# schematic.net
KiCad netlist of a schematic drawn in EAGLE
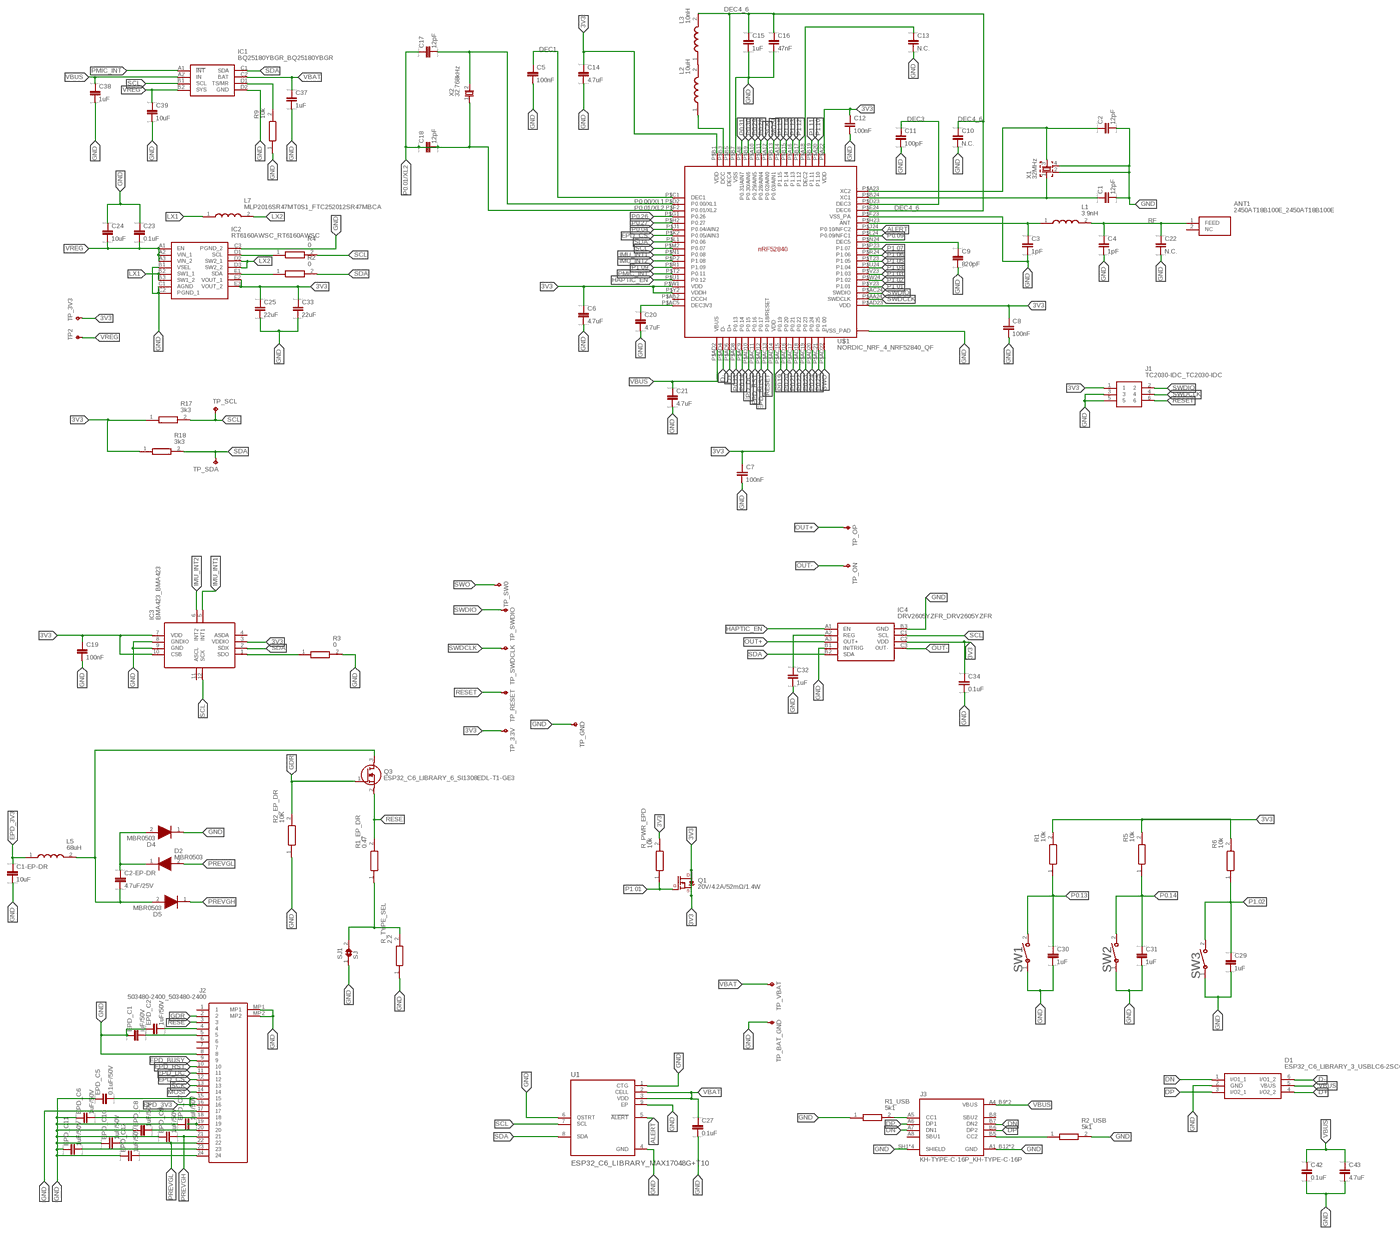
[diagram p0: schematic, sheet 1, overview]
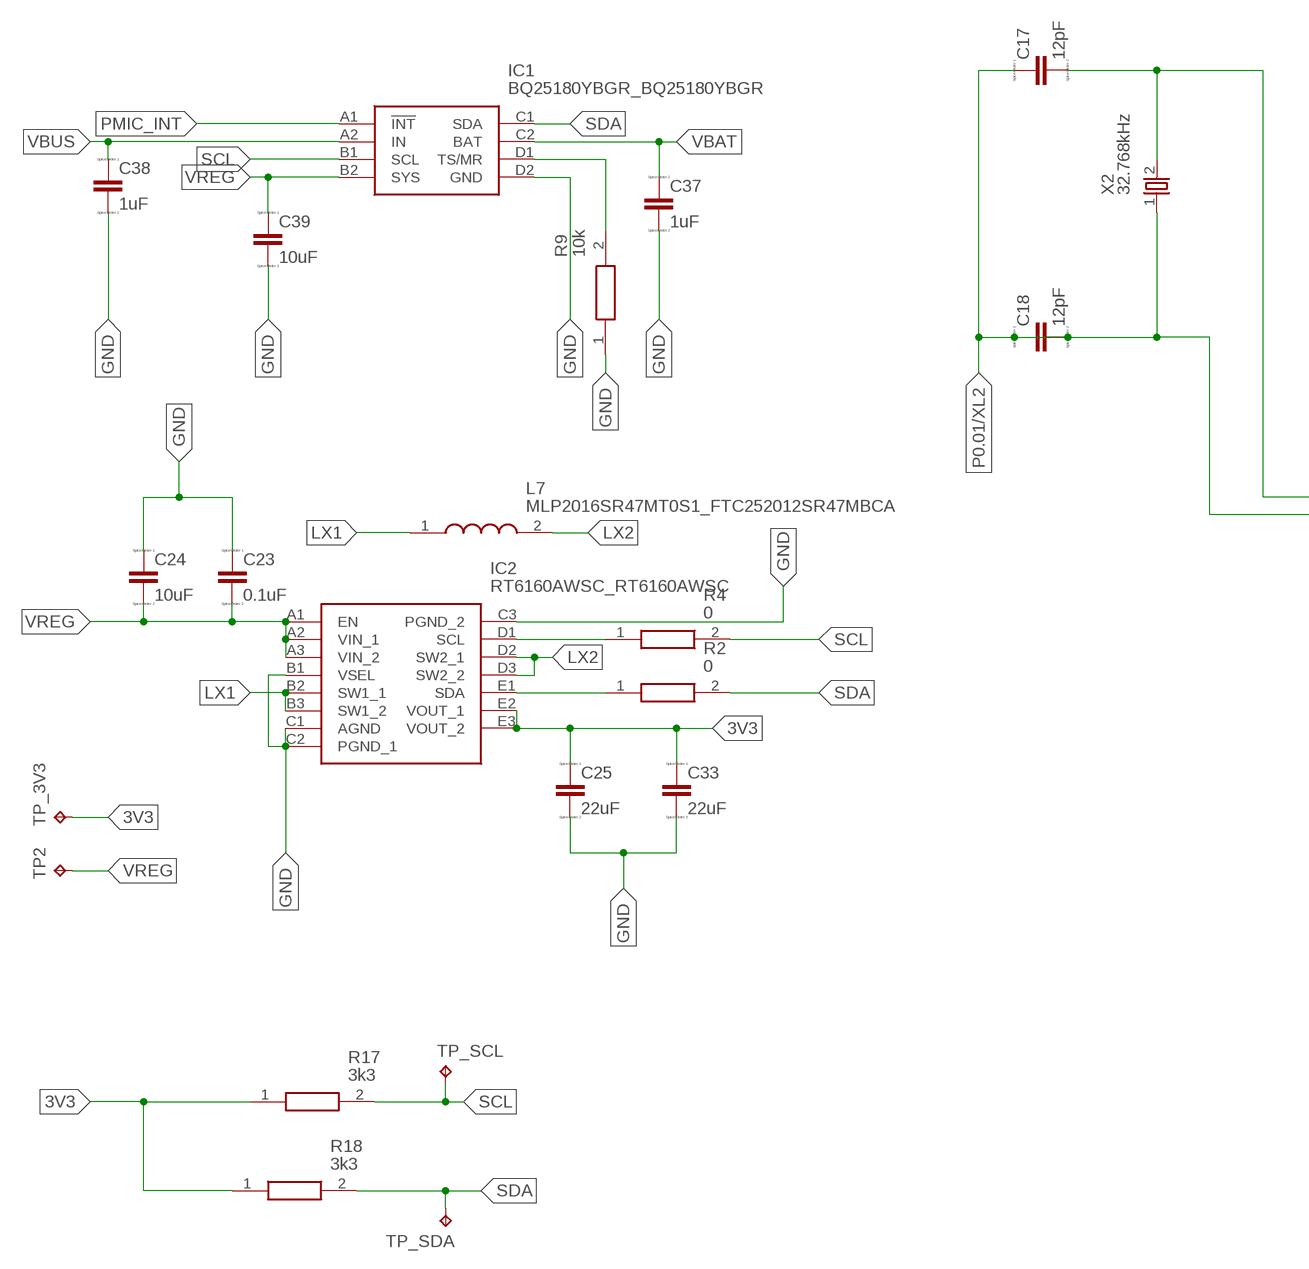
[diagram p1: schematic, sheet 1, part 1 of 4]
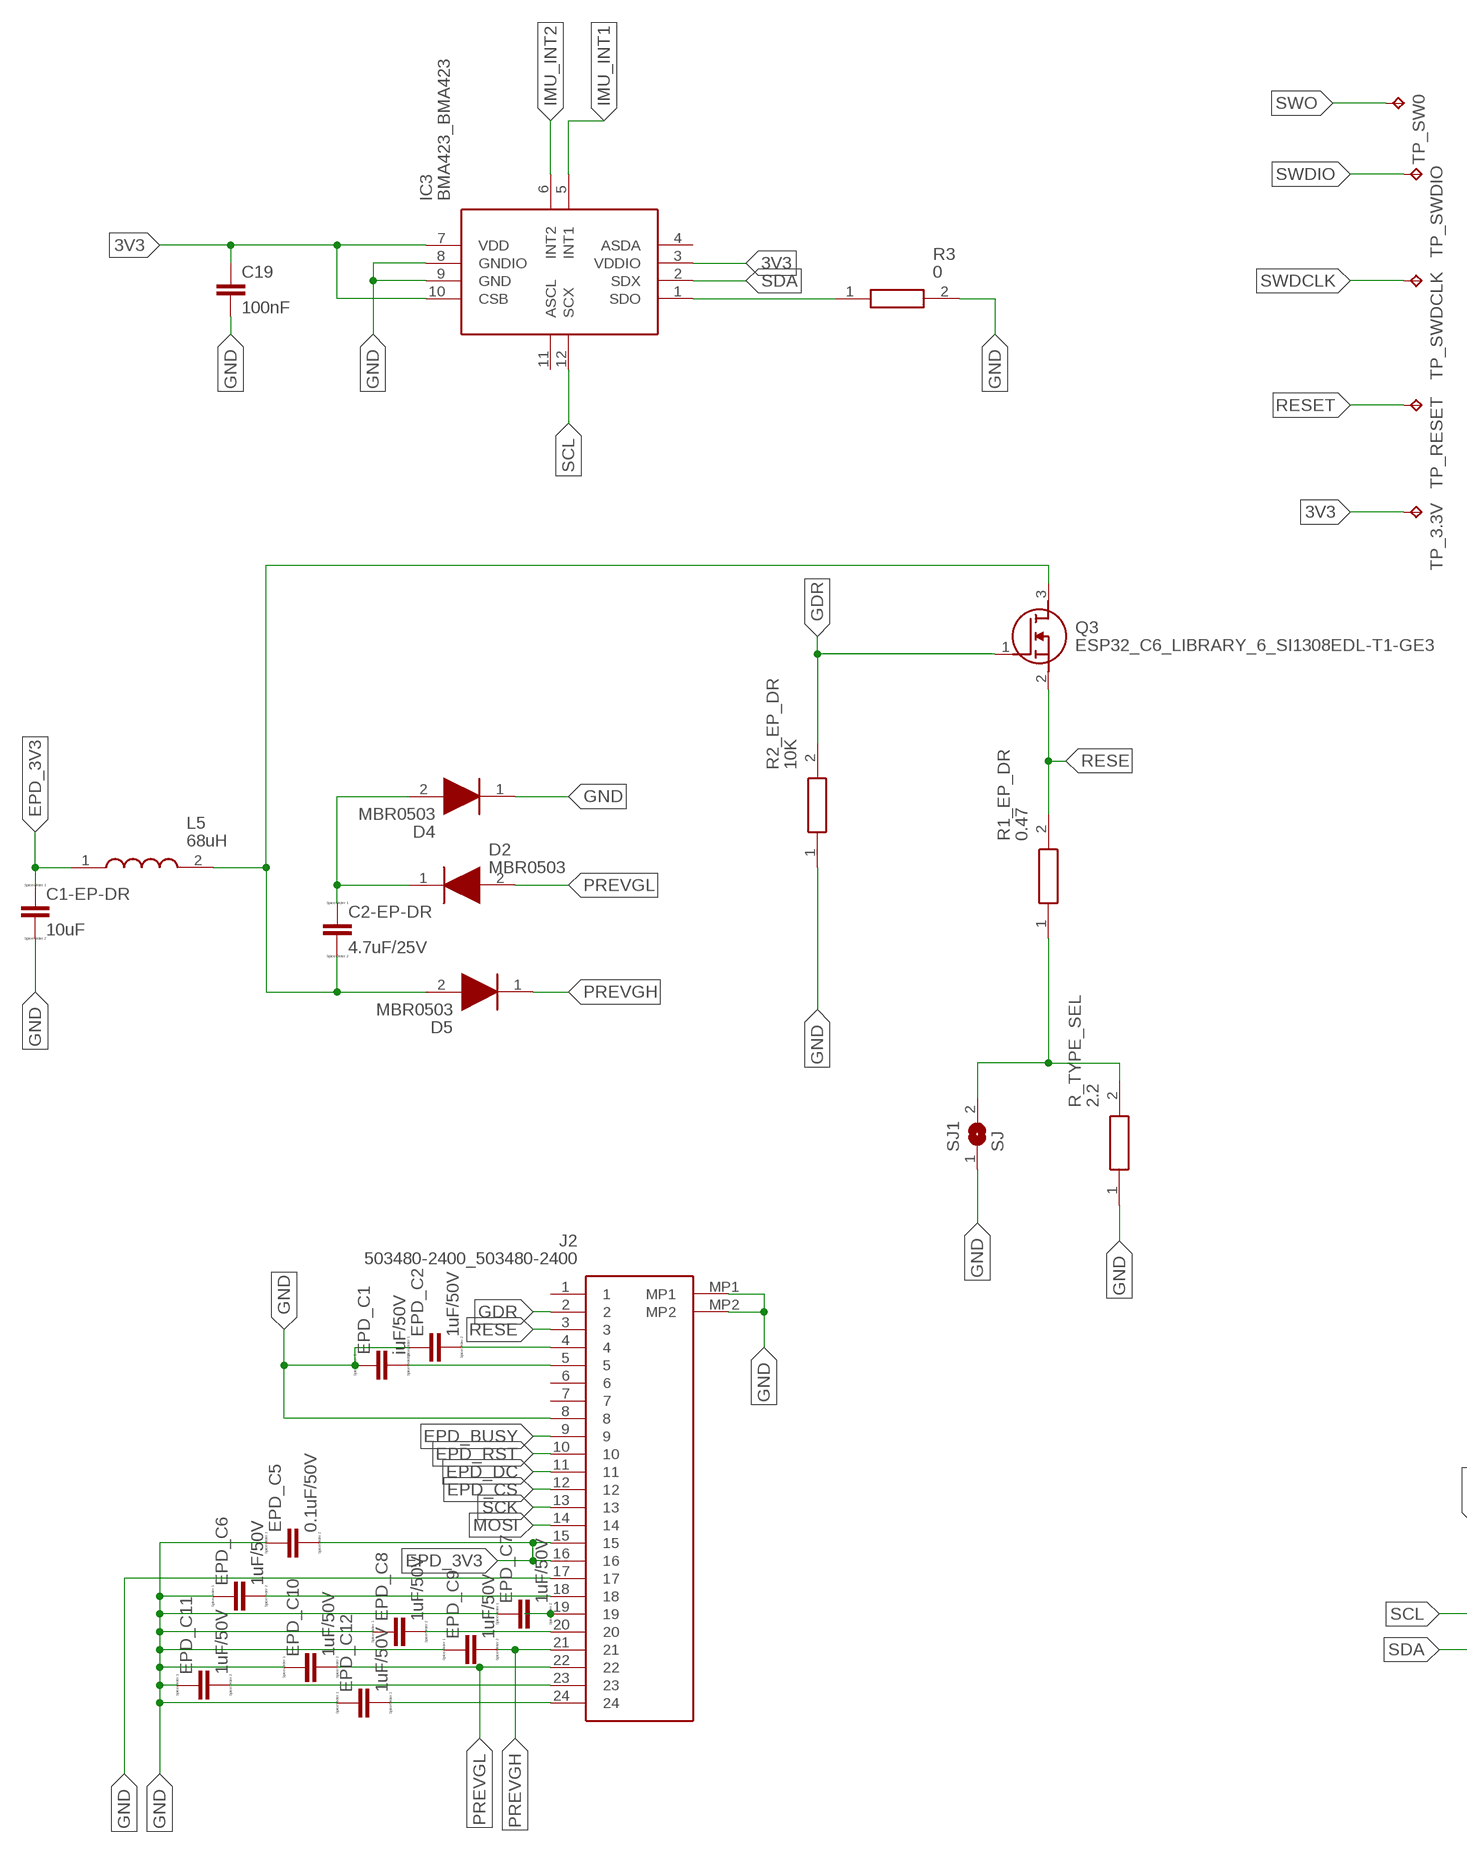
[diagram p2: schematic, sheet 1, part 2 of 4]
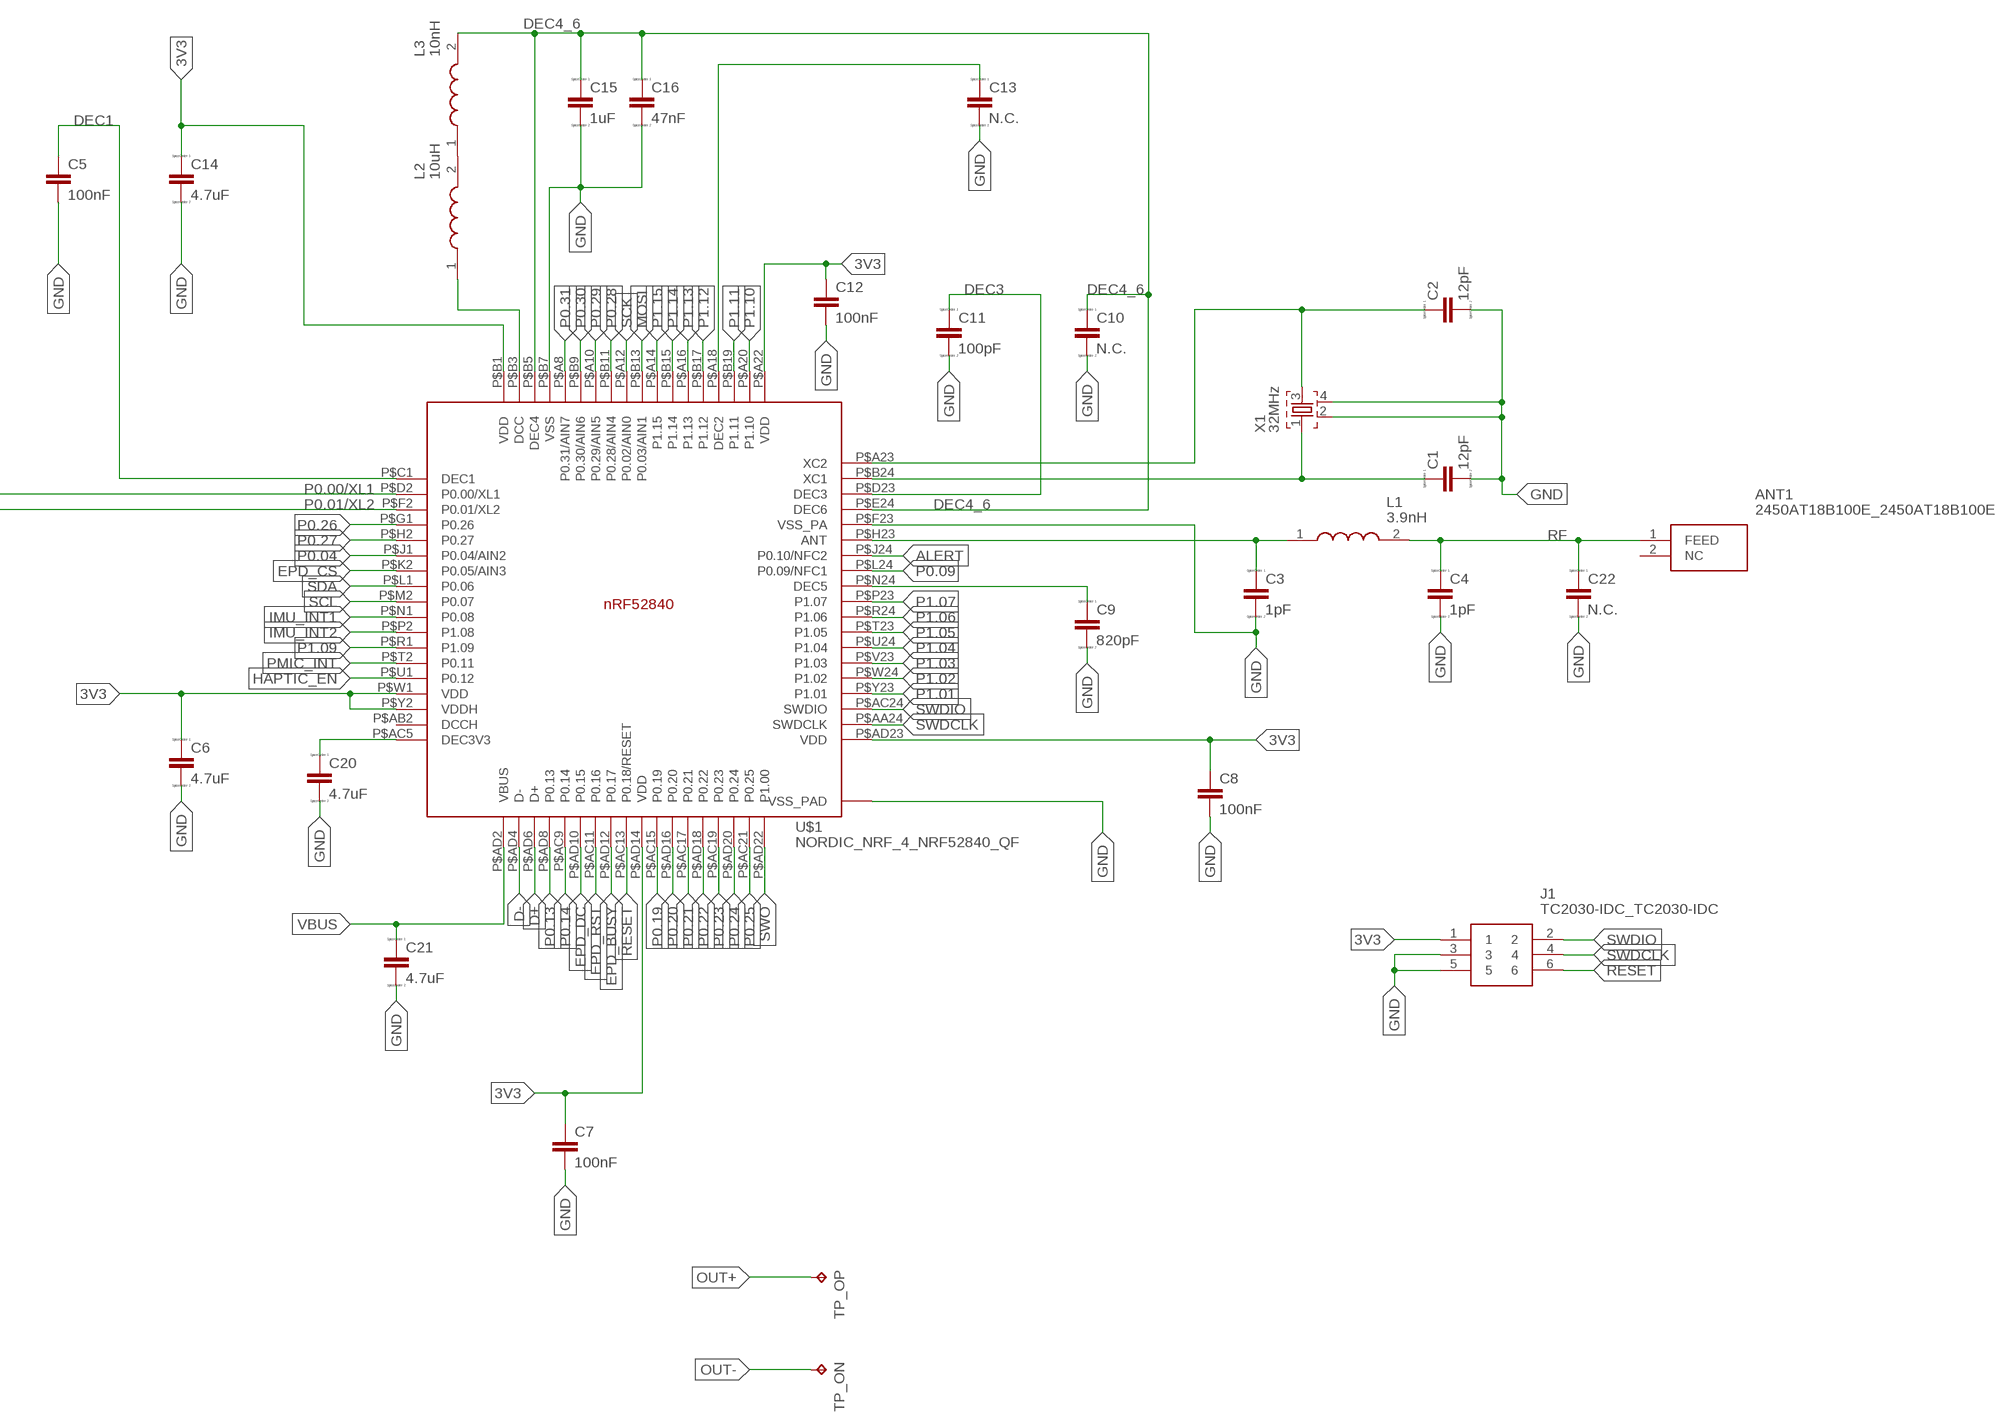
[diagram p3: schematic, sheet 1, part 3 of 4]
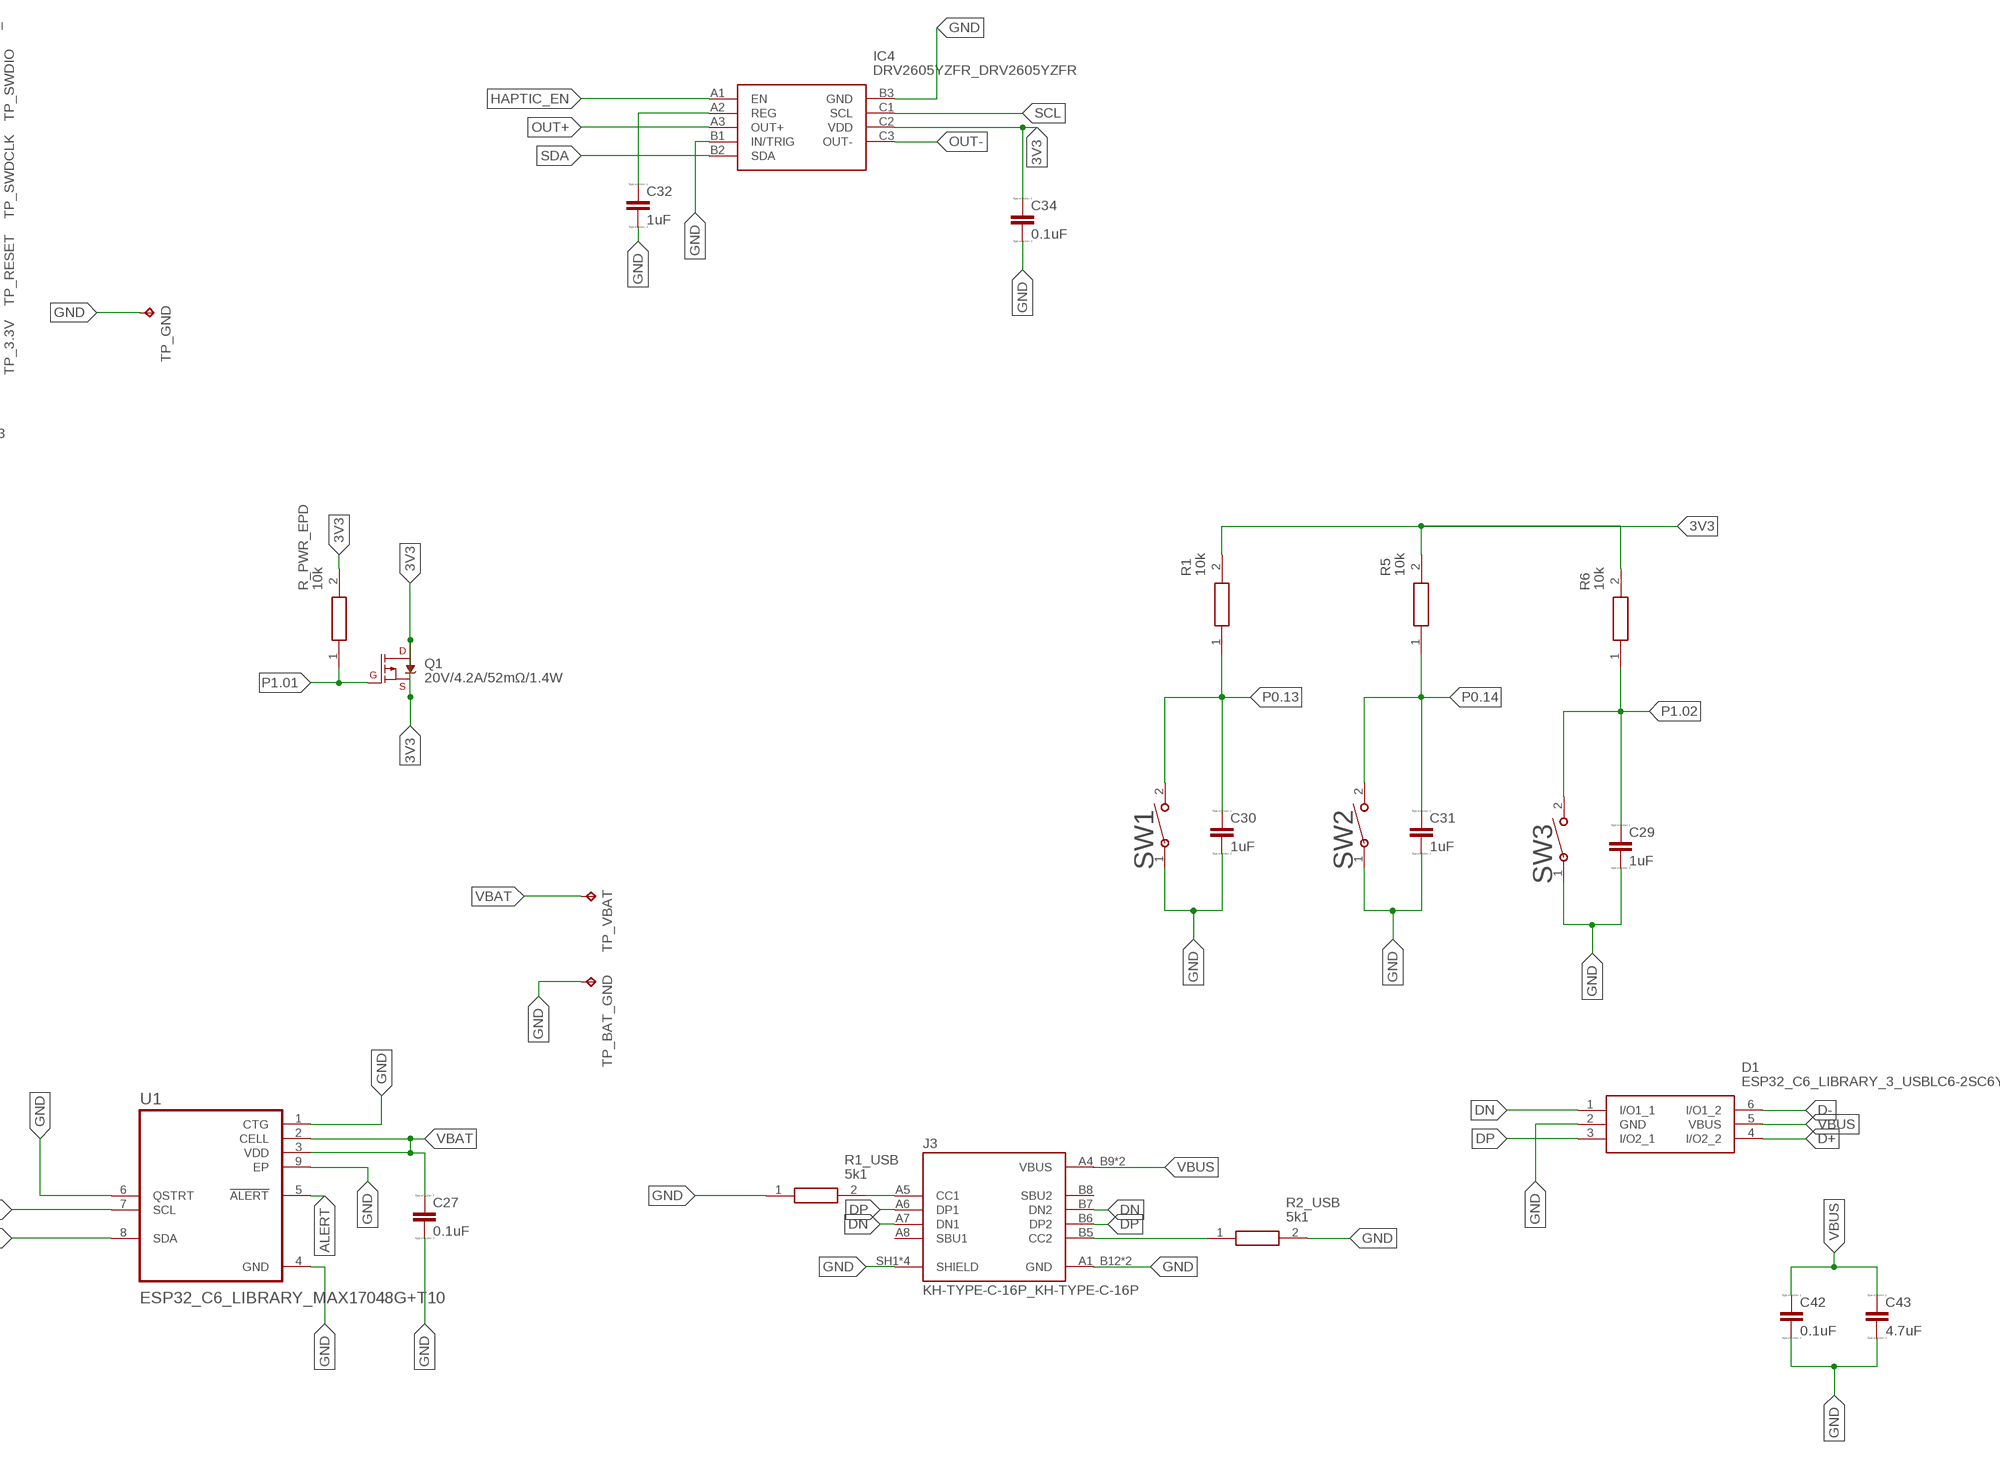
[diagram p4: schematic, sheet 1, part 4 of 4]

(export (version "E")
  (design (tool "Eeschema 10.0.6"))
  (components
    (comp (ref "ANT1")
      (value "2450AT18B100E_2450AT18B100E")
      (footprint "eagle-import:2450AT18B100E_ANTC3216X140N")
      (fields
        (field (name "ARROW_PART_NUMBER") "2450AT18B100E")
        (field (name "MOUSER_PART_NUMBER") "609-2450AT18B100E")
      )
      (libsource (lib "eagle-import") (part "2450AT18B100E_2450AT18B100E"))
    )
    (comp (ref "C1")
      (value "12pF")
      (footprint "eagle-import:ESP32_C6_LIBRARY_1_ESP32_WROVER_EAGLE-LTSPICE_C0402")
      (libsource (lib "eagle-import") (part "ESP32_C6_LIBRARY_1_ESP32_WROVER_EAGLE-LTSPICE_CC0402"))
    )
    (comp (ref "C1-EP-DR")
      (value "10uF")
      (footprint "eagle-import:ESP32_C6_LIBRARY_1_ESP32_WROVER_EAGLE-LTSPICE_C0402")
      (libsource (lib "eagle-import") (part "ESP32_C6_LIBRARY_1_ESP32_WROVER_EAGLE-LTSPICE_CC0402"))
    )
    (comp (ref "C2")
      (value "12pF")
      (footprint "eagle-import:ESP32_C6_LIBRARY_1_ESP32_WROVER_EAGLE-LTSPICE_C0402")
      (libsource (lib "eagle-import") (part "ESP32_C6_LIBRARY_1_ESP32_WROVER_EAGLE-LTSPICE_CC0402"))
    )
    (comp (ref "C2-EP-DR")
      (value "4.7uF/25V")
      (footprint "eagle-import:ESP32_C6_LIBRARY_1_ESP32_WROVER_EAGLE-LTSPICE_C0402")
      (libsource (lib "eagle-import") (part "ESP32_C6_LIBRARY_1_ESP32_WROVER_EAGLE-LTSPICE_CC0402"))
    )
    (comp (ref "C3")
      (value "1pF")
      (footprint "eagle-import:ESP32_C6_LIBRARY_1_ESP32_WROVER_EAGLE-LTSPICE_C0402")
      (libsource (lib "eagle-import") (part "ESP32_C6_LIBRARY_1_ESP32_WROVER_EAGLE-LTSPICE_CC0402"))
    )
    (comp (ref "C4")
      (value "1pF")
      (footprint "eagle-import:ESP32_C6_LIBRARY_1_ESP32_WROVER_EAGLE-LTSPICE_C0402")
      (libsource (lib "eagle-import") (part "ESP32_C6_LIBRARY_1_ESP32_WROVER_EAGLE-LTSPICE_CC0402"))
    )
    (comp (ref "C5")
      (value "100nF")
      (footprint "eagle-import:NORDIC_NRF_3_RESC0201_L")
      (libsource (lib "eagle-import") (part "NORDIC_NRF_3_CAPACITOR_0201_L"))
    )
    (comp (ref "C6")
      (value "4.7uF")
      (footprint "eagle-import:ESP32_C6_LIBRARY_1_ESP32_WROVER_EAGLE-LTSPICE_C0402")
      (libsource (lib "eagle-import") (part "ESP32_C6_LIBRARY_1_ESP32_WROVER_EAGLE-LTSPICE_CC0402"))
    )
    (comp (ref "C7")
      (value "100nF")
      (footprint "eagle-import:NORDIC_NRF_3_RESC0201_L")
      (libsource (lib "eagle-import") (part "NORDIC_NRF_3_CAPACITOR_0201_L"))
    )
    (comp (ref "C8")
      (value "100nF")
      (footprint "eagle-import:NORDIC_NRF_3_RESC0201_L")
      (libsource (lib "eagle-import") (part "NORDIC_NRF_3_CAPACITOR_0201_L"))
    )
    (comp (ref "C9")
      (value "820pF")
      (footprint "eagle-import:ESP32_C6_LIBRARY_1_ESP32_WROVER_EAGLE-LTSPICE_C0402")
      (libsource (lib "eagle-import") (part "ESP32_C6_LIBRARY_1_ESP32_WROVER_EAGLE-LTSPICE_CC0402"))
    )
    (comp (ref "C10")
      (value "N.C.")
      (footprint "eagle-import:ESP32_C6_LIBRARY_1_ESP32_WROVER_EAGLE-LTSPICE_C0402")
      (libsource (lib "eagle-import") (part "ESP32_C6_LIBRARY_1_ESP32_WROVER_EAGLE-LTSPICE_CC0402"))
    )
    (comp (ref "C11")
      (value "100pF")
      (footprint "eagle-import:ESP32_C6_LIBRARY_1_ESP32_WROVER_EAGLE-LTSPICE_C0402")
      (libsource (lib "eagle-import") (part "ESP32_C6_LIBRARY_1_ESP32_WROVER_EAGLE-LTSPICE_CC0402"))
    )
    (comp (ref "C12")
      (value "100nF")
      (footprint "eagle-import:NORDIC_NRF_3_RESC0201_L")
      (libsource (lib "eagle-import") (part "NORDIC_NRF_3_CAPACITOR_0201_L"))
    )
    (comp (ref "C13")
      (value "N.C.")
      (footprint "eagle-import:ESP32_C6_LIBRARY_1_ESP32_WROVER_EAGLE-LTSPICE_C0402")
      (libsource (lib "eagle-import") (part "ESP32_C6_LIBRARY_1_ESP32_WROVER_EAGLE-LTSPICE_CC0402"))
    )
    (comp (ref "C14")
      (value "4.7uF")
      (footprint "eagle-import:ESP32_C6_LIBRARY_1_ESP32_WROVER_EAGLE-LTSPICE_C0402")
      (libsource (lib "eagle-import") (part "ESP32_C6_LIBRARY_1_ESP32_WROVER_EAGLE-LTSPICE_CC0402"))
    )
    (comp (ref "C15")
      (value "1uF")
      (footprint "eagle-import:ESP32_C6_LIBRARY_1_ESP32_WROVER_EAGLE-LTSPICE_C0402")
      (libsource (lib "eagle-import") (part "ESP32_C6_LIBRARY_1_ESP32_WROVER_EAGLE-LTSPICE_CC0402"))
    )
    (comp (ref "C16")
      (value "47nF")
      (footprint "eagle-import:ESP32_C6_LIBRARY_1_ESP32_WROVER_EAGLE-LTSPICE_C0402")
      (libsource (lib "eagle-import") (part "ESP32_C6_LIBRARY_1_ESP32_WROVER_EAGLE-LTSPICE_CC0402"))
    )
    (comp (ref "C17")
      (value "12pF")
      (footprint "eagle-import:ESP32_C6_LIBRARY_1_ESP32_WROVER_EAGLE-LTSPICE_C0402")
      (libsource (lib "eagle-import") (part "ESP32_C6_LIBRARY_1_ESP32_WROVER_EAGLE-LTSPICE_CC0402"))
    )
    (comp (ref "C18")
      (value "12pF")
      (footprint "eagle-import:ESP32_C6_LIBRARY_1_ESP32_WROVER_EAGLE-LTSPICE_C0402")
      (libsource (lib "eagle-import") (part "ESP32_C6_LIBRARY_1_ESP32_WROVER_EAGLE-LTSPICE_CC0402"))
    )
    (comp (ref "C19")
      (value "100nF")
      (footprint "eagle-import:NORDIC_NRF_3_RESC0201_L")
      (libsource (lib "eagle-import") (part "NORDIC_NRF_3_CAPACITOR_0201_L"))
    )
    (comp (ref "C20")
      (value "4.7uF")
      (footprint "eagle-import:ESP32_C6_LIBRARY_1_ESP32_WROVER_EAGLE-LTSPICE_C0402")
      (libsource (lib "eagle-import") (part "ESP32_C6_LIBRARY_1_ESP32_WROVER_EAGLE-LTSPICE_CC0402"))
    )
    (comp (ref "C21")
      (value "4.7uF")
      (footprint "eagle-import:ESP32_C6_LIBRARY_1_ESP32_WROVER_EAGLE-LTSPICE_C0402")
      (libsource (lib "eagle-import") (part "ESP32_C6_LIBRARY_1_ESP32_WROVER_EAGLE-LTSPICE_CC0402"))
    )
    (comp (ref "C22")
      (value "N.C.")
      (footprint "eagle-import:ESP32_C6_LIBRARY_1_ESP32_WROVER_EAGLE-LTSPICE_C0402")
      (libsource (lib "eagle-import") (part "ESP32_C6_LIBRARY_1_ESP32_WROVER_EAGLE-LTSPICE_CC0402"))
    )
    (comp (ref "C23")
      (value "0.1uF")
      (footprint "eagle-import:ESP32_C6_LIBRARY_1_ESP32_WROVER_EAGLE-LTSPICE_C0402")
      (libsource (lib "eagle-import") (part "ESP32_C6_LIBRARY_1_ESP32_WROVER_EAGLE-LTSPICE_CC0402"))
    )
    (comp (ref "C24")
      (value "10uF")
      (footprint "eagle-import:ESP32_C6_LIBRARY_1_ESP32_WROVER_EAGLE-LTSPICE_C0402")
      (libsource (lib "eagle-import") (part "ESP32_C6_LIBRARY_1_ESP32_WROVER_EAGLE-LTSPICE_CC0402"))
    )
    (comp (ref "C25")
      (value "22uF")
      (footprint "eagle-import:ESP32_C6_LIBRARY_1_ESP32_WROVER_EAGLE-LTSPICE_C0402")
      (libsource (lib "eagle-import") (part "ESP32_C6_LIBRARY_1_ESP32_WROVER_EAGLE-LTSPICE_CC0402"))
    )
    (comp (ref "C27")
      (value "0.1uF")
      (footprint "eagle-import:ESP32_C6_LIBRARY_1_ESP32_WROVER_EAGLE-LTSPICE_C0402")
      (libsource (lib "eagle-import") (part "ESP32_C6_LIBRARY_1_ESP32_WROVER_EAGLE-LTSPICE_CC0402"))
    )
    (comp (ref "C29")
      (value "1uF")
      (footprint "eagle-import:ESP32_C6_LIBRARY_1_ESP32_WROVER_EAGLE-LTSPICE_C0402")
      (libsource (lib "eagle-import") (part "ESP32_C6_LIBRARY_1_ESP32_WROVER_EAGLE-LTSPICE_CC0402"))
    )
    (comp (ref "C30")
      (value "1uF")
      (footprint "eagle-import:ESP32_C6_LIBRARY_1_ESP32_WROVER_EAGLE-LTSPICE_C0402")
      (libsource (lib "eagle-import") (part "ESP32_C6_LIBRARY_1_ESP32_WROVER_EAGLE-LTSPICE_CC0402"))
    )
    (comp (ref "C31")
      (value "1uF")
      (footprint "eagle-import:ESP32_C6_LIBRARY_1_ESP32_WROVER_EAGLE-LTSPICE_C0402")
      (libsource (lib "eagle-import") (part "ESP32_C6_LIBRARY_1_ESP32_WROVER_EAGLE-LTSPICE_CC0402"))
    )
    (comp (ref "C32")
      (value "1uF")
      (footprint "eagle-import:ESP32_C6_LIBRARY_1_ESP32_WROVER_EAGLE-LTSPICE_C0402")
      (libsource (lib "eagle-import") (part "ESP32_C6_LIBRARY_1_ESP32_WROVER_EAGLE-LTSPICE_CC0402"))
    )
    (comp (ref "C33")
      (value "22uF")
      (footprint "eagle-import:ESP32_C6_LIBRARY_1_ESP32_WROVER_EAGLE-LTSPICE_C0402")
      (libsource (lib "eagle-import") (part "ESP32_C6_LIBRARY_1_ESP32_WROVER_EAGLE-LTSPICE_CC0402"))
    )
    (comp (ref "C34")
      (value "0.1uF")
      (footprint "eagle-import:ESP32_C6_LIBRARY_1_ESP32_WROVER_EAGLE-LTSPICE_C0402")
      (libsource (lib "eagle-import") (part "ESP32_C6_LIBRARY_1_ESP32_WROVER_EAGLE-LTSPICE_CC0402"))
    )
    (comp (ref "C37")
      (value "1uF")
      (footprint "eagle-import:ESP32_C6_LIBRARY_1_ESP32_WROVER_EAGLE-LTSPICE_C0402")
      (libsource (lib "eagle-import") (part "ESP32_C6_LIBRARY_1_ESP32_WROVER_EAGLE-LTSPICE_CC0402"))
    )
    (comp (ref "C38")
      (value "1uF")
      (footprint "eagle-import:ESP32_C6_LIBRARY_1_ESP32_WROVER_EAGLE-LTSPICE_C0402")
      (libsource (lib "eagle-import") (part "ESP32_C6_LIBRARY_1_ESP32_WROVER_EAGLE-LTSPICE_CC0402"))
    )
    (comp (ref "C39")
      (value "10uF")
      (footprint "eagle-import:ESP32_C6_LIBRARY_1_ESP32_WROVER_EAGLE-LTSPICE_C0402")
      (libsource (lib "eagle-import") (part "ESP32_C6_LIBRARY_1_ESP32_WROVER_EAGLE-LTSPICE_CC0402"))
    )
    (comp (ref "C42")
      (value "0.1uF")
      (footprint "eagle-import:ESP32_C6_LIBRARY_1_ESP32_WROVER_EAGLE-LTSPICE_C0402")
      (libsource (lib "eagle-import") (part "ESP32_C6_LIBRARY_1_ESP32_WROVER_EAGLE-LTSPICE_CC0402"))
    )
    (comp (ref "C43")
      (value "4.7uF")
      (footprint "eagle-import:ESP32_C6_LIBRARY_1_ESP32_WROVER_EAGLE-LTSPICE_C0402")
      (libsource (lib "eagle-import") (part "ESP32_C6_LIBRARY_1_ESP32_WROVER_EAGLE-LTSPICE_CC0402"))
    )
    (comp (ref "D1")
      (value "ESP32_C6_LIBRARY_3_USBLC6-2SC6Y")
      (footprint "eagle-import:ESP32_C6_LIBRARY_3_SOT95P280X145-6N")
      (fields (field (name "MF") "STMicroelectronics") (field (name "MP") "USBLC6-2SC6Y"))
      (libsource (lib "eagle-import") (part "ESP32_C6_LIBRARY_3_USBLC6-2SC6Y"))
    )
    (comp (ref "D2")
      (value "MBR0503")
      (footprint "eagle-import:ESP32_C6_LIBRARY_5_SOD3716X135N")
      (fields (field (name "MF") "ON Semiconductor") (field (name "MP") "MBR0530"))
      (libsource (lib "eagle-import") (part "ESP32_C6_LIBRARY_5_MBR0530"))
    )
    (comp (ref "D4")
      (value "MBR0503")
      (footprint "eagle-import:ESP32_C6_LIBRARY_5_SOD3716X135N")
      (fields (field (name "MF") "ON Semiconductor") (field (name "MP") "MBR0530"))
      (libsource (lib "eagle-import") (part "ESP32_C6_LIBRARY_5_MBR0530"))
    )
    (comp (ref "D5")
      (value "MBR0503")
      (footprint "eagle-import:ESP32_C6_LIBRARY_5_SOD3716X135N")
      (fields (field (name "MF") "ON Semiconductor") (field (name "MP") "MBR0530"))
      (libsource (lib "eagle-import") (part "ESP32_C6_LIBRARY_5_MBR0530"))
    )
    (comp (ref "EPD_C1")
      (value "iuF/50V")
      (footprint "eagle-import:ESP32_C6_LIBRARY_1_ESP32_WROVER_EAGLE-LTSPICE_C0402")
      (libsource (lib "eagle-import") (part "ESP32_C6_LIBRARY_1_ESP32_WROVER_EAGLE-LTSPICE_CC0402"))
    )
    (comp (ref "EPD_C2")
      (value "1uF/50V")
      (footprint "eagle-import:ESP32_C6_LIBRARY_1_ESP32_WROVER_EAGLE-LTSPICE_C0402")
      (libsource (lib "eagle-import") (part "ESP32_C6_LIBRARY_1_ESP32_WROVER_EAGLE-LTSPICE_CC0402"))
    )
    (comp (ref "EPD_C5")
      (value "0.1uF/50V")
      (footprint "eagle-import:ESP32_C6_LIBRARY_1_ESP32_WROVER_EAGLE-LTSPICE_C0402")
      (libsource (lib "eagle-import") (part "ESP32_C6_LIBRARY_1_ESP32_WROVER_EAGLE-LTSPICE_CC0402"))
    )
    (comp (ref "EPD_C6")
      (value "1uF/50V")
      (footprint "eagle-import:ESP32_C6_LIBRARY_1_ESP32_WROVER_EAGLE-LTSPICE_C0402")
      (libsource (lib "eagle-import") (part "ESP32_C6_LIBRARY_1_ESP32_WROVER_EAGLE-LTSPICE_CC0402"))
    )
    (comp (ref "EPD_C7")
      (value "1uF/50V")
      (footprint "eagle-import:ESP32_C6_LIBRARY_1_ESP32_WROVER_EAGLE-LTSPICE_C0402")
      (libsource (lib "eagle-import") (part "ESP32_C6_LIBRARY_1_ESP32_WROVER_EAGLE-LTSPICE_CC0402"))
    )
    (comp (ref "EPD_C8")
      (value "1uF/50V")
      (footprint "eagle-import:ESP32_C6_LIBRARY_1_ESP32_WROVER_EAGLE-LTSPICE_C0402")
      (libsource (lib "eagle-import") (part "ESP32_C6_LIBRARY_1_ESP32_WROVER_EAGLE-LTSPICE_CC0402"))
    )
    (comp (ref "EPD_C9")
      (value "1uF/50V")
      (footprint "eagle-import:ESP32_C6_LIBRARY_1_ESP32_WROVER_EAGLE-LTSPICE_C0402")
      (libsource (lib "eagle-import") (part "ESP32_C6_LIBRARY_1_ESP32_WROVER_EAGLE-LTSPICE_CC0402"))
    )
    (comp (ref "EPD_C10")
      (value "1uF/50V")
      (footprint "eagle-import:ESP32_C6_LIBRARY_1_ESP32_WROVER_EAGLE-LTSPICE_C0402")
      (libsource (lib "eagle-import") (part "ESP32_C6_LIBRARY_1_ESP32_WROVER_EAGLE-LTSPICE_CC0402"))
    )
    (comp (ref "EPD_C11")
      (value "1uF/50V")
      (footprint "eagle-import:ESP32_C6_LIBRARY_1_ESP32_WROVER_EAGLE-LTSPICE_C0402")
      (libsource (lib "eagle-import") (part "ESP32_C6_LIBRARY_1_ESP32_WROVER_EAGLE-LTSPICE_CC0402"))
    )
    (comp (ref "EPD_C12")
      (value "1uF/50V")
      (footprint "eagle-import:ESP32_C6_LIBRARY_1_ESP32_WROVER_EAGLE-LTSPICE_C0402")
      (libsource (lib "eagle-import") (part "ESP32_C6_LIBRARY_1_ESP32_WROVER_EAGLE-LTSPICE_CC0402"))
    )
    (comp (ref "IC1")
      (value "BQ25180YBGR_BQ25180YBGR")
      (footprint "eagle-import:BQ25180YBGR_BGA8C40P2X4_100X155X50")
      (fields
        (field (name "ARROW_PART_NUMBER") "BQ25180YBGR")
        (field (name "MOUSER_PART_NUMBER") "595-BQ25180YBGR")
      )
      (libsource (lib "eagle-import") (part "BQ25180YBGR_BQ25180YBGR"))
    )
    (comp (ref "IC2")
      (value "RT6160AWSC_RT6160AWSC")
      (footprint "eagle-import:RT6160AWSC_BGA15C40P3X5_140X230X60")
      (fields
        (field (name "MANUFACTURER_PART_NUMBER") "RT6160AWSC")
        (field (name "MOUSER_PART_NUMBER") "835-RT6160AWSC")
      )
      (libsource (lib "eagle-import") (part "RT6160AWSC_RT6160AWSC"))
    )
    (comp (ref "IC3")
      (value "BMA423_BMA423")
      (footprint "eagle-import:BMA423_BMA423")
      (fields (field (name "ARROW_PART_NUMBER") "BMA423") (field (name "MOUSER_PART_NUMBER") "262-BMA423"))
      (libsource (lib "eagle-import") (part "BMA423_BMA423"))
    )
    (comp (ref "IC4")
      (value "DRV2605YZFR_DRV2605YZFR")
      (footprint "eagle-import:DRV2605YZFR_BGA9C50P3X3_144X144X62")
      (fields (field (name "ARROW_PART_NUMBER") "DRV2605YZFR"))
      (libsource (lib "eagle-import") (part "DRV2605YZFR_DRV2605YZFR"))
    )
    (comp (ref "J1")
      (value "TC2030-IDC_TC2030-IDC")
      (footprint "eagle-import:TC2030-IDC_TC2030IDC")
      (fields (field (name "MANUFACTURER_PART_NUMBER") "TC2030-IDC"))
      (libsource (lib "eagle-import") (part "TC2030-IDC_TC2030-IDC"))
    )
    (comp (ref "J2")
      (value "503480-2400_503480-2400")
      (footprint "eagle-import:503480-2400_5034802400")
      (fields
        (field (name "MANUFACTURER_PART_NUMBER") "503480-2400")
        (field (name "MOUSER_PART_NUMBER") "538-503480-2400")
      )
      (libsource (lib "eagle-import") (part "503480-2400_503480-2400"))
    )
    (comp (ref "J3")
      (value "KH-TYPE-C-16P_KH-TYPE-C-16P")
      (footprint "eagle-import:KH-TYPE-C-16P_KINGHELM_KH-TYPE-C-16P")
      (fields (field (name "MF") "kinghelm") (field (name "MP") "KH-TYPE-C-16P"))
      (libsource (lib "eagle-import") (part "KH-TYPE-C-16P_KH-TYPE-C-16P"))
    )
    (comp (ref "L1")
      (value "3.9nH")
      (footprint "eagle-import:MLP2016SR47MT0S1_INDC2016X100N")
      (fields (field (name "MANUFACTURER_PART_NUMBER") "FTC252012SR47MBCA"))
      (libsource (lib "eagle-import") (part "MLP2016SR47MT0S1_FTC252012SR47MBCA"))
    )
    (comp (ref "L2")
      (value "10uH")
      (footprint "eagle-import:MLP2016SR47MT0S1_INDC2016X100N")
      (fields (field (name "MANUFACTURER_PART_NUMBER") "FTC252012SR47MBCA"))
      (libsource (lib "eagle-import") (part "MLP2016SR47MT0S1_FTC252012SR47MBCA"))
    )
    (comp (ref "L3")
      (value "10nH")
      (footprint "eagle-import:MLP2016SR47MT0S1_INDC2016X100N")
      (fields (field (name "MANUFACTURER_PART_NUMBER") "FTC252012SR47MBCA"))
      (libsource (lib "eagle-import") (part "MLP2016SR47MT0S1_FTC252012SR47MBCA"))
    )
    (comp (ref "L5")
      (value "68uH")
      (footprint "eagle-import:MLP2016SR47MT0S1_INDC2016X100N")
      (fields (field (name "MANUFACTURER_PART_NUMBER") "FTC252012SR47MBCA"))
      (libsource (lib "eagle-import") (part "MLP2016SR47MT0S1_FTC252012SR47MBCA"))
    )
    (comp (ref "L7")
      (value "MLP2016SR47MT0S1_FTC252012SR47MBCA")
      (footprint "eagle-import:MLP2016SR47MT0S1_INDC2016X100N")
      (fields (field (name "MANUFACTURER_PART_NUMBER") "FTC252012SR47MBCA"))
      (libsource (lib "eagle-import") (part "MLP2016SR47MT0S1_FTC252012SR47MBCA"))
    )
    (comp (ref "Q1")
      (value "20V/4.2A/52mΩ/1.4W")
      (footprint "eagle-import:ESP32_C6_LIBRARY_4_ESP32_C6_LIBRARY_4_ESP32_C6_LIBRARY_4_ESP32_C6_LIBRARY_4_ESP32_WROVER_SPARKFUN-DISCRETESEMI_SOT23-3")
      (libsource (lib "eagle-import") (part "ESP32_C6_LIBRARY_4_ESP32_WROVER_SPARKFUN-DISCRETESEMI_MOSFET_PCH-DMG2305UX-7"))
    )
    (comp (ref "Q3")
      (value "ESP32_C6_LIBRARY_6_SI1308EDL-T1-GE3")
      (footprint "eagle-import:ESP32_C6_LIBRARY_6_SOT65P210X110-3N")
      (fields (field (name "MF") "Vishay Siliconix") (field (name "MP") "SI1308EDL-T1-GE3"))
      (libsource (lib "eagle-import") (part "ESP32_C6_LIBRARY_6_SI1308EDL-T1-GE3"))
    )
    (comp (ref "R1")
      (value "10k")
      (footprint "eagle-import:ERA-1AEB3401C_0201")
      (libsource (lib "eagle-import") (part "ERA-1AEB3401C_CPF0201D7K68C1"))
    )
    (comp (ref "R1_EP_DR")
      (value "0.47")
      (footprint "eagle-import:ERA-1AEB3401C_0201")
      (libsource (lib "eagle-import") (part "ERA-1AEB3401C_CPF0201D7K68C1"))
    )
    (comp (ref "R1_USB")
      (value "5k1")
      (footprint "eagle-import:ERA-1AEB3401C_0201")
      (libsource (lib "eagle-import") (part "ERA-1AEB3401C_CPF0201D7K68C1"))
    )
    (comp (ref "R2")
      (value "0")
      (footprint "eagle-import:ERA-1AEB3401C_0201")
      (libsource (lib "eagle-import") (part "ERA-1AEB3401C_CPF0201D7K68C1"))
    )
    (comp (ref "R2_EP_DR")
      (value "10K")
      (footprint "eagle-import:ERA-1AEB3401C_0201")
      (libsource (lib "eagle-import") (part "ERA-1AEB3401C_CPF0201D7K68C1"))
    )
    (comp (ref "R2_USB")
      (value "5k1")
      (footprint "eagle-import:ERA-1AEB3401C_0201")
      (libsource (lib "eagle-import") (part "ERA-1AEB3401C_CPF0201D7K68C1"))
    )
    (comp (ref "R3")
      (value "0")
      (footprint "eagle-import:ERA-1AEB3401C_0201")
      (libsource (lib "eagle-import") (part "ERA-1AEB3401C_CPF0201D7K68C1"))
    )
    (comp (ref "R4")
      (value "0")
      (footprint "eagle-import:ERA-1AEB3401C_0201")
      (libsource (lib "eagle-import") (part "ERA-1AEB3401C_CPF0201D7K68C1"))
    )
    (comp (ref "R5")
      (value "10k")
      (footprint "eagle-import:ERA-1AEB3401C_0201")
      (libsource (lib "eagle-import") (part "ERA-1AEB3401C_CPF0201D7K68C1"))
    )
    (comp (ref "R6")
      (value "10k")
      (footprint "eagle-import:ERA-1AEB3401C_0201")
      (libsource (lib "eagle-import") (part "ERA-1AEB3401C_CPF0201D7K68C1"))
    )
    (comp (ref "R9")
      (value "10k")
      (footprint "eagle-import:CPF0201D7K68C1_0201")
      (libsource (lib "eagle-import") (part "CPF0201D7K68C1_CPF0201D7K68C1"))
    )
    (comp (ref "R17")
      (value "3k3")
      (footprint "eagle-import:ERA-1AEB3401C_0201")
      (libsource (lib "eagle-import") (part "ERA-1AEB3401C_CPF0201D7K68C1"))
    )
    (comp (ref "R18")
      (value "3k3")
      (footprint "eagle-import:ERA-1AEB3401C_0201")
      (libsource (lib "eagle-import") (part "ERA-1AEB3401C_CPF0201D7K68C1"))
    )
    (comp (ref "R_PWR_EPD")
      (value "10k")
      (footprint "eagle-import:ERA-1AEB3401C_0201")
      (libsource (lib "eagle-import") (part "ERA-1AEB3401C_CPF0201D7K68C1"))
    )
    (comp (ref "R_TYPE_SEL")
      (value "2.2")
      (footprint "eagle-import:ERA-1AEB3401C_0201")
      (libsource (lib "eagle-import") (part "ERA-1AEB3401C_CPF0201D7K68C1"))
    )
    (comp (ref "SJ1")
      (value "SJ")
      (footprint "eagle-import:ESP32_C6_LIBRARY_7_JUMPER_SJ")
      (libsource (lib "eagle-import") (part "ESP32_C6_LIBRARY_7_JUMPER_SJ"))
    )
    (comp (ref "SW1")
      (value "2025-10-22_07-23-44_LIBRARY_EVP-AKE31ASW_EVP-AKE31A_PAN")
      (footprint "eagle-import:2025-10-22_07-23-44_LIBRARY_SW_EVP-AKE31A_PAN")
      (fields
        (field (name "MANUFACTURER_PART_NUMBER") "EVP-AKE31A")
        (field (name "COPYRIGHT") "Copyright (C) 2025 Ultra Librarian. All rights reserved.")
      )
      (libsource (lib "eagle-import") (part "2025-10-22_07-23-44_LIBRARY_EVP-AKE31ASW_EVP-AKE31A_PAN"))
    )
    (comp (ref "SW2")
      (value "2025-10-22_07-23-44_LIBRARY_EVP-AKE31ASW_EVP-AKE31A_PAN")
      (footprint "eagle-import:2025-10-22_07-23-44_LIBRARY_SW_EVP-AKE31A_PAN")
      (fields
        (field (name "MANUFACTURER_PART_NUMBER") "EVP-AKE31A")
        (field (name "COPYRIGHT") "Copyright (C) 2025 Ultra Librarian. All rights reserved.")
      )
      (libsource (lib "eagle-import") (part "2025-10-22_07-23-44_LIBRARY_EVP-AKE31ASW_EVP-AKE31A_PAN"))
    )
    (comp (ref "SW3")
      (value "2025-10-22_07-23-44_LIBRARY_EVP-AKE31ASW_EVP-AKE31A_PAN")
      (footprint "eagle-import:2025-10-22_07-23-44_LIBRARY_SW_EVP-AKE31A_PAN")
      (fields
        (field (name "MANUFACTURER_PART_NUMBER") "EVP-AKE31A")
        (field (name "COPYRIGHT") "Copyright (C) 2025 Ultra Librarian. All rights reserved.")
      )
      (libsource (lib "eagle-import") (part "2025-10-22_07-23-44_LIBRARY_EVP-AKE31ASW_EVP-AKE31A_PAN"))
    )
    (comp (ref "TP2")
      (value "HECTOR_WATCH_1_TPTP20R")
      (footprint "eagle-import:HECTOR_WATCH_1_TP20R")
      (libsource (lib "eagle-import") (part "HECTOR_WATCH_1_TPTP20R"))
    )
    (comp (ref "TP_3.3V")
      (value "HECTOR_WATCH_1_TPTP20R")
      (footprint "eagle-import:HECTOR_WATCH_1_TP20R")
      (libsource (lib "eagle-import") (part "HECTOR_WATCH_1_TPTP20R"))
    )
    (comp (ref "TP_3V3")
      (value "HECTOR_WATCH_1_TPTP20R")
      (footprint "eagle-import:HECTOR_WATCH_1_TP20R")
      (libsource (lib "eagle-import") (part "HECTOR_WATCH_1_TPTP20R"))
    )
    (comp (ref "TP_BAT_GND")
      (value "HECTOR_WATCH_1_TPTP20R")
      (footprint "eagle-import:HECTOR_WATCH_1_TP20R")
      (libsource (lib "eagle-import") (part "HECTOR_WATCH_1_TPTP20R"))
    )
    (comp (ref "TP_GND")
      (value "HECTOR_WATCH_1_TPTP20R")
      (footprint "eagle-import:HECTOR_WATCH_1_TP20R")
      (libsource (lib "eagle-import") (part "HECTOR_WATCH_1_TPTP20R"))
    )
    (comp (ref "TP_ON")
      (value "HECTOR_WATCH_1_TPTP20R")
      (footprint "eagle-import:HECTOR_WATCH_1_TP20R")
      (libsource (lib "eagle-import") (part "HECTOR_WATCH_1_TPTP20R"))
    )
    (comp (ref "TP_OP")
      (value "HECTOR_WATCH_1_TPTP20R")
      (footprint "eagle-import:HECTOR_WATCH_1_TP20R")
      (libsource (lib "eagle-import") (part "HECTOR_WATCH_1_TPTP20R"))
    )
    (comp (ref "TP_RESET")
      (value "HECTOR_WATCH_1_TPTP20R")
      (footprint "eagle-import:HECTOR_WATCH_1_TP20R")
      (libsource (lib "eagle-import") (part "HECTOR_WATCH_1_TPTP20R"))
    )
    (comp (ref "TP_SCL")
      (value "HECTOR_WATCH_1_TPTP20R")
      (footprint "eagle-import:HECTOR_WATCH_1_TP20R")
      (libsource (lib "eagle-import") (part "HECTOR_WATCH_1_TPTP20R"))
    )
    (comp (ref "TP_SDA")
      (value "HECTOR_WATCH_1_TPTP20R")
      (footprint "eagle-import:HECTOR_WATCH_1_TP20R")
      (libsource (lib "eagle-import") (part "HECTOR_WATCH_1_TPTP20R"))
    )
    (comp (ref "TP_SW0")
      (value "HECTOR_WATCH_1_TPTP20R")
      (footprint "eagle-import:HECTOR_WATCH_1_TP20R")
      (libsource (lib "eagle-import") (part "HECTOR_WATCH_1_TPTP20R"))
    )
    (comp (ref "TP_SWDCLK")
      (value "HECTOR_WATCH_1_TPTP20R")
      (footprint "eagle-import:HECTOR_WATCH_1_TP20R")
      (libsource (lib "eagle-import") (part "HECTOR_WATCH_1_TPTP20R"))
    )
    (comp (ref "TP_SWDIO")
      (value "HECTOR_WATCH_1_TPTP20R")
      (footprint "eagle-import:HECTOR_WATCH_1_TP20R")
      (libsource (lib "eagle-import") (part "HECTOR_WATCH_1_TPTP20R"))
    )
    (comp (ref "TP_VBAT")
      (value "HECTOR_WATCH_1_TPTP20R")
      (footprint "eagle-import:HECTOR_WATCH_1_TP20R")
      (libsource (lib "eagle-import") (part "HECTOR_WATCH_1_TPTP20R"))
    )
    (comp (ref "U$1")
      (value "NORDIC_NRF_4_NRF52840_QF")
      (footprint "eagle-import:NORDIC_NRF_4_AQFN50P700X700X85_HS-74N")
      (libsource (lib "eagle-import") (part "NORDIC_NRF_4_NRF52840_QF"))
    )
    (comp (ref "U1")
      (value "ESP32_C6_LIBRARY_MAX17048G+T10")
      (footprint "eagle-import:ESP32_C6_LIBRARY_SON50P200X200X80-9N")
      (fields (field (name "MF") "Analog Devices") (field (name "MP") "MAX17048G+T10"))
      (libsource (lib "eagle-import") (part "ESP32_C6_LIBRARY_MAX17048G+T10"))
    )
    (comp (ref "X1")
      (value "32MHz")
      (footprint "eagle-import:NORDIC_NRF_BT-XTAL_2016_N")
      (libsource (lib "eagle-import") (part "NORDIC_NRF_XTAL_32MHZ"))
    )
    (comp (ref "X2")
      (value "32.768kHz")
      (footprint "eagle-import:NORDIC_NRF_1_XTAL_3215_N")
      (libsource (lib "eagle-import") (part "NORDIC_NRF_1_XTAL_32KHZ"))
    )
  )
  (nets
    (net (code "1") (name "/DEC1") (class "Default")
      (node (ref "C5") (pin "1") (pinfunction "1_1") (pintype "passive"))
      (node (ref "U$1") (pin "P$C1") (pinfunction "DEC1_P$C1") (pintype "power_in"))
    )
    (net (code "2") (name "/DEC3") (class "Default")
      (node (ref "C11") (pin "1") (pinfunction "1_1") (pintype "passive"))
      (node (ref "U$1") (pin "P$D23") (pinfunction "DEC3_P$D23") (pintype "bidirectional"))
    )
    (net (code "3") (name "/DEC4_6") (class "Default")
      (node (ref "C10") (pin "1") (pinfunction "1_1") (pintype "passive"))
      (node (ref "C15") (pin "1") (pinfunction "1_1") (pintype "passive"))
      (node (ref "C16") (pin "1") (pinfunction "1_1") (pintype "passive"))
      (node (ref "L3") (pin "2") (pinfunction "2_2") (pintype "bidirectional"))
      (node (ref "U$1") (pin "P$B5") (pinfunction "DEC4_P$B5") (pintype "power_in"))
      (node (ref "U$1") (pin "P$E24") (pinfunction "DEC6_P$E24") (pintype "bidirectional"))
    )
    (net (code "4") (name "/P0.00{slash}XL1") (class "Default")
      (node (ref "C17") (pin "2") (pinfunction "2_2") (pintype "passive"))
      (node (ref "U$1") (pin "P$D2") (pinfunction "P0.00/XL1_P$D2") (pintype "bidirectional"))
      (node (ref "X2") (pin "2") (pinfunction "2_2") (pintype "passive"))
    )
    (net (code "5") (name "/RF") (class "Default")
      (node (ref "ANT1") (pin "1") (pinfunction "FEED_1") (pintype "input"))
      (node (ref "C22") (pin "1") (pinfunction "1_1") (pintype "passive"))
      (node (ref "C4") (pin "1") (pinfunction "1_1") (pintype "passive"))
      (node (ref "L1") (pin "2") (pinfunction "2_2") (pintype "bidirectional"))
    )
    (net (code "6") (name "3V3") (class "Default")
      (node (ref "C12") (pin "1") (pinfunction "1_1") (pintype "passive"))
      (node (ref "C14") (pin "1") (pinfunction "1_1") (pintype "passive"))
      (node (ref "C19") (pin "1") (pinfunction "1_1") (pintype "passive"))
      (node (ref "C25") (pin "1") (pinfunction "1_1") (pintype "passive"))
      (node (ref "C33") (pin "1") (pinfunction "1_1") (pintype "passive"))
      (node (ref "C34") (pin "1") (pinfunction "1_1") (pintype "passive"))
      (node (ref "C6") (pin "1") (pinfunction "1_1") (pintype "passive"))
      (node (ref "C7") (pin "1") (pinfunction "1_1") (pintype "passive"))
      (node (ref "C8") (pin "1") (pinfunction "1_1") (pintype "passive"))
      (node (ref "IC2") (pin "E2") (pinfunction "VOUT_1_E2") (pintype "bidirectional"))
      (node (ref "IC2") (pin "E3") (pinfunction "VOUT_2_E3") (pintype "bidirectional"))
      (node (ref "IC3") (pin "10") (pinfunction "CSB_10") (pintype "bidirectional"))
      (node (ref "IC3") (pin "3") (pinfunction "VDDIO_3") (pintype "bidirectional"))
      (node (ref "IC3") (pin "7") (pinfunction "VDD_7") (pintype "bidirectional"))
      (node (ref "IC4") (pin "C2") (pinfunction "VDD_C2") (pintype "bidirectional"))
      (node (ref "J1") (pin "1") (pinfunction "1_1") (pintype "bidirectional"))
      (node (ref "Q1") (pin "2") (pinfunction "S_2") (pintype "bidirectional"))
      (node (ref "Q1") (pin "3") (pinfunction "D_3") (pintype "bidirectional"))
      (node (ref "R1") (pin "2") (pinfunction "2_2") (pintype "bidirectional"))
      (node (ref "R17") (pin "1") (pinfunction "1_1") (pintype "bidirectional"))
      (node (ref "R18") (pin "1") (pinfunction "1_1") (pintype "bidirectional"))
      (node (ref "R5") (pin "2") (pinfunction "2_2") (pintype "bidirectional"))
      (node (ref "R6") (pin "2") (pinfunction "2_2") (pintype "bidirectional"))
      (node (ref "R_PWR_EPD") (pin "2") (pinfunction "2_2") (pintype "bidirectional"))
      (node (ref "TP_3.3V") (pin "TP") (pinfunction "TP_TP") (pintype "input"))
      (node (ref "TP_3V3") (pin "TP") (pinfunction "TP_TP") (pintype "input"))
      (node (ref "U$1") (pin "P$A22") (pinfunction "VDD_P$A22") (pintype "power_in"))
      (node (ref "U$1") (pin "P$AD14") (pinfunction "VDD_P$AD14") (pintype "power_in"))
      (node (ref "U$1") (pin "P$AD23") (pinfunction "VDD_P$AD23") (pintype "power_in"))
      (node (ref "U$1") (pin "P$B1") (pinfunction "VDD_P$B1") (pintype "power_in"))
      (node (ref "U$1") (pin "P$W1") (pinfunction "VDD_P$W1") (pintype "power_in"))
      (node (ref "U$1") (pin "P$Y2") (pinfunction "VDDH_P$Y2") (pintype "power_in"))
    )
    (net (code "7") (name "ALERT") (class "Default")
      (node (ref "U$1") (pin "P$J24") (pinfunction "P0.10/NFC2_P$J24") (pintype "bidirectional"))
      (node (ref "U1") (pin "5") (pinfunction "~{ALERT}_5") (pintype "output"))
    )
    (net (code "8") (name "D+") (class "Default")
      (node (ref "D1") (pin "4") (pinfunction "I/O2_2_4") (pintype "bidirectional"))
      (node (ref "U$1") (pin "P$AD6") (pinfunction "D+_P$AD6") (pintype "bidirectional"))
    )
    (net (code "9") (name "D-") (class "Default")
      (node (ref "D1") (pin "6") (pinfunction "I/O1_2_6") (pintype "bidirectional"))
      (node (ref "U$1") (pin "P$AD4") (pinfunction "D-_P$AD4") (pintype "bidirectional"))
    )
    (net (code "10") (name "DN") (class "Default")
      (node (ref "D1") (pin "1") (pinfunction "I/O1_1_1") (pintype "bidirectional"))
      (node (ref "J3") (pin "A7") (pinfunction "DN1_A7") (pintype "bidirectional"))
      (node (ref "J3") (pin "B7") (pinfunction "DN2_B7") (pintype "bidirectional"))
    )
    (net (code "11") (name "DP") (class "Default")
      (node (ref "D1") (pin "3") (pinfunction "I/O2_1_3") (pintype "bidirectional"))
      (node (ref "J3") (pin "A6") (pinfunction "DP1_A6") (pintype "bidirectional"))
      (node (ref "J3") (pin "B6") (pinfunction "DP2_B6") (pintype "bidirectional"))
    )
    (net (code "12") (name "EPD_3V3") (class "Default")
      (node (ref "C1-EP-DR") (pin "1") (pinfunction "1_1") (pintype "passive"))
      (node (ref "EPD_C5") (pin "2") (pinfunction "2_2") (pintype "passive"))
      (node (ref "J2") (pin "15") (pinfunction "15_15") (pintype "bidirectional"))
      (node (ref "J2") (pin "16") (pinfunction "16_16") (pintype "bidirectional"))
      (node (ref "L5") (pin "1") (pinfunction "1_1") (pintype "bidirectional"))
    )
    (net (code "13") (name "EPD_BUSY") (class "Default")
      (node (ref "J2") (pin "9") (pinfunction "9_9") (pintype "bidirectional"))
      (node (ref "U$1") (pin "P$AD12") (pinfunction "P0.17_P$AD12") (pintype "bidirectional"))
    )
    (net (code "14") (name "EPD_CS") (class "Default")
      (node (ref "J2") (pin "12") (pinfunction "12_12") (pintype "bidirectional"))
      (node (ref "U$1") (pin "P$K2") (pinfunction "P0.05/AIN3_P$K2") (pintype "bidirectional"))
    )
    (net (code "15") (name "EPD_DC") (class "Default")
      (node (ref "J2") (pin "11") (pinfunction "11_11") (pintype "bidirectional"))
      (node (ref "U$1") (pin "P$AD10") (pinfunction "P0.15_P$AD10") (pintype "bidirectional"))
    )
    (net (code "16") (name "EPD_RST") (class "Default")
      (node (ref "J2") (pin "10") (pinfunction "10_10") (pintype "bidirectional"))
      (node (ref "U$1") (pin "P$AC11") (pinfunction "P0.16_P$AC11") (pintype "bidirectional"))
    )
    (net (code "17") (name "GDR") (class "Default")
      (node (ref "J2") (pin "2") (pinfunction "2_2") (pintype "bidirectional"))
      (node (ref "Q3") (pin "1") (pinfunction "G_1") (pintype "bidirectional"))
      (node (ref "R2_EP_DR") (pin "2") (pinfunction "2_2") (pintype "bidirectional"))
    )
    (net (code "18") (name "GND") (class "Default")
      (node (ref "C1") (pin "2") (pinfunction "2_2") (pintype "passive"))
      (node (ref "C1-EP-DR") (pin "2") (pinfunction "2_2") (pintype "passive"))
      (node (ref "C10") (pin "2") (pinfunction "2_2") (pintype "passive"))
      (node (ref "C11") (pin "2") (pinfunction "2_2") (pintype "passive"))
      (node (ref "C12") (pin "2") (pinfunction "2_2") (pintype "passive"))
      (node (ref "C13") (pin "2") (pinfunction "2_2") (pintype "passive"))
      (node (ref "C14") (pin "2") (pinfunction "2_2") (pintype "passive"))
      (node (ref "C15") (pin "2") (pinfunction "2_2") (pintype "passive"))
      (node (ref "C16") (pin "2") (pinfunction "2_2") (pintype "passive"))
      (node (ref "C19") (pin "2") (pinfunction "2_2") (pintype "passive"))
      (node (ref "C2") (pin "2") (pinfunction "2_2") (pintype "passive"))
      (node (ref "C20") (pin "2") (pinfunction "2_2") (pintype "passive"))
      (node (ref "C21") (pin "2") (pinfunction "2_2") (pintype "passive"))
      (node (ref "C22") (pin "2") (pinfunction "2_2") (pintype "passive"))
      (node (ref "C23") (pin "1") (pinfunction "1_1") (pintype "passive"))
      (node (ref "C24") (pin "1") (pinfunction "1_1") (pintype "passive"))
      (node (ref "C25") (pin "2") (pinfunction "2_2") (pintype "passive"))
      (node (ref "C27") (pin "2") (pinfunction "2_2") (pintype "passive"))
      (node (ref "C29") (pin "2") (pinfunction "2_2") (pintype "passive"))
      (node (ref "C3") (pin "2") (pinfunction "2_2") (pintype "passive"))
      (node (ref "C30") (pin "2") (pinfunction "2_2") (pintype "passive"))
      (node (ref "C31") (pin "2") (pinfunction "2_2") (pintype "passive"))
      (node (ref "C32") (pin "2") (pinfunction "2_2") (pintype "passive"))
      (node (ref "C33") (pin "2") (pinfunction "2_2") (pintype "passive"))
      (node (ref "C34") (pin "2") (pinfunction "2_2") (pintype "passive"))
      (node (ref "C37") (pin "2") (pinfunction "2_2") (pintype "passive"))
      (node (ref "C38") (pin "2") (pinfunction "2_2") (pintype "passive"))
      (node (ref "C39") (pin "2") (pinfunction "2_2") (pintype "passive"))
      (node (ref "C4") (pin "2") (pinfunction "2_2") (pintype "passive"))
      (node (ref "C42") (pin "2") (pinfunction "2_2") (pintype "passive"))
      (node (ref "C43") (pin "2") (pinfunction "2_2") (pintype "passive"))
      (node (ref "C5") (pin "2") (pinfunction "2_2") (pintype "passive"))
      (node (ref "C6") (pin "2") (pinfunction "2_2") (pintype "passive"))
      (node (ref "C7") (pin "2") (pinfunction "2_2") (pintype "passive"))
      (node (ref "C8") (pin "2") (pinfunction "2_2") (pintype "passive"))
      (node (ref "C9") (pin "2") (pinfunction "2_2") (pintype "passive"))
      (node (ref "D1") (pin "2") (pinfunction "GND_2") (pintype "bidirectional"))
      (node (ref "D4") (pin "1") (pinfunction "K_1") (pintype "bidirectional"))
      (node (ref "EPD_C1") (pin "1") (pinfunction "1_1") (pintype "passive"))
      (node (ref "EPD_C10") (pin "1") (pinfunction "1_1") (pintype "passive"))
      (node (ref "EPD_C11") (pin "1") (pinfunction "1_1") (pintype "passive"))
      (node (ref "EPD_C12") (pin "1") (pinfunction "1_1") (pintype "passive"))
      (node (ref "EPD_C2") (pin "1") (pinfunction "1_1") (pintype "passive"))
      (node (ref "EPD_C5") (pin "1") (pinfunction "1_1") (pintype "passive"))
      (node (ref "EPD_C6") (pin "1") (pinfunction "1_1") (pintype "passive"))
      (node (ref "EPD_C7") (pin "1") (pinfunction "1_1") (pintype "passive"))
      (node (ref "EPD_C8") (pin "1") (pinfunction "1_1") (pintype "passive"))
      (node (ref "EPD_C9") (pin "1") (pinfunction "1_1") (pintype "passive"))
      (node (ref "IC1") (pin "D2") (pinfunction "GND_D2") (pintype "bidirectional"))
      (node (ref "IC2") (pin "B1") (pinfunction "VSEL_B1") (pintype "bidirectional"))
      (node (ref "IC2") (pin "C1") (pinfunction "AGND_C1") (pintype "bidirectional"))
      (node (ref "IC2") (pin "C2") (pinfunction "PGND_1_C2") (pintype "bidirectional"))
      (node (ref "IC2") (pin "C3") (pinfunction "PGND_2_C3") (pintype "bidirectional"))
      (node (ref "IC3") (pin "8") (pinfunction "GNDIO_8") (pintype "bidirectional"))
      (node (ref "IC3") (pin "9") (pinfunction "GND_9") (pintype "bidirectional"))
      (node (ref "IC4") (pin "B1") (pinfunction "IN/TRIG_B1") (pintype "bidirectional"))
      (node (ref "IC4") (pin "B3") (pinfunction "GND_B3") (pintype "bidirectional"))
      (node (ref "J1") (pin "3") (pinfunction "3_3") (pintype "bidirectional"))
      (node (ref "J1") (pin "5") (pinfunction "5_5") (pintype "bidirectional"))
      (node (ref "J2") (pin "17") (pinfunction "17_17") (pintype "bidirectional"))
      (node (ref "J2") (pin "8") (pinfunction "8_8") (pintype "bidirectional"))
      (node (ref "J2") (pin "MP1") (pinfunction "MP1_MP1") (pintype "bidirectional"))
      (node (ref "J2") (pin "MP2") (pinfunction "MP2_MP2") (pintype "bidirectional"))
      (node (ref "J3") (pin "A12_B1") (pinfunction "GND_A12_B1") (pintype "power_in"))
      (node (ref "J3") (pin "A1_B12") (pinfunction "GND_A1_B12") (pintype "power_in"))
      (node (ref "J3") (pin "SH1") (pinfunction "SHIELD_SH1") (pintype "passive"))
      (node (ref "J3") (pin "SH2") (pinfunction "SHIELD_SH2") (pintype "passive"))
      (node (ref "J3") (pin "SH3") (pinfunction "SHIELD_SH3") (pintype "passive"))
      (node (ref "J3") (pin "SH4") (pinfunction "SHIELD_SH4") (pintype "passive"))
      (node (ref "R1_USB") (pin "1") (pinfunction "1_1") (pintype "bidirectional"))
      (node (ref "R2_EP_DR") (pin "1") (pinfunction "1_1") (pintype "bidirectional"))
      (node (ref "R2_USB") (pin "2") (pinfunction "2_2") (pintype "bidirectional"))
      (node (ref "R3") (pin "2") (pinfunction "2_2") (pintype "bidirectional"))
      (node (ref "R9") (pin "1") (pinfunction "1_1") (pintype "bidirectional"))
      (node (ref "R_TYPE_SEL") (pin "1") (pinfunction "1_1") (pintype "bidirectional"))
      (node (ref "SJ1") (pin "1") (pinfunction "1_1") (pintype "passive"))
      (node (ref "SW1") (pin "1") (pinfunction "1_1") (pintype "passive"))
      (node (ref "SW2") (pin "1") (pinfunction "1_1") (pintype "passive"))
      (node (ref "SW3") (pin "1") (pinfunction "1_1") (pintype "passive"))
      (node (ref "TP_BAT_GND") (pin "TP") (pinfunction "TP_TP") (pintype "input"))
      (node (ref "TP_GND") (pin "TP") (pinfunction "TP_TP") (pintype "input"))
      (node (ref "U$1") (pin "P$74") (pinfunction "VSS_PAD_P$74") (pintype "bidirectional"))
      (node (ref "U$1") (pin "P$75") (pinfunction "VSS_PAD_P$75") (pintype "bidirectional"))
      (node (ref "U$1") (pin "P$76") (pinfunction "VSS_PAD_P$76") (pintype "bidirectional"))
      (node (ref "U$1") (pin "P$77") (pinfunction "VSS_PAD_P$77") (pintype "bidirectional"))
      (node (ref "U$1") (pin "P$78") (pinfunction "VSS_PAD_P$78") (pintype "bidirectional"))
      (node (ref "U$1") (pin "P$79") (pinfunction "VSS_PAD_P$79") (pintype "bidirectional"))
      (node (ref "U$1") (pin "P$80") (pinfunction "VSS_PAD_P$80") (pintype "bidirectional"))
      (node (ref "U$1") (pin "P$81") (pinfunction "VSS_PAD_P$81") (pintype "bidirectional"))
      (node (ref "U$1") (pin "P$82") (pinfunction "VSS_PAD_P$82") (pintype "bidirectional"))
      (node (ref "U$1") (pin "P$83") (pinfunction "VSS_PAD_P$83") (pintype "bidirectional"))
      (node (ref "U$1") (pin "P$84") (pinfunction "VSS_PAD_P$84") (pintype "bidirectional"))
      (node (ref "U$1") (pin "P$85") (pinfunction "VSS_PAD_P$85") (pintype "bidirectional"))
      (node (ref "U$1") (pin "P$86") (pinfunction "VSS_PAD_P$86") (pintype "bidirectional"))
      (node (ref "U$1") (pin "P$87") (pinfunction "VSS_PAD_P$87") (pintype "bidirectional"))
      (node (ref "U$1") (pin "P$88") (pinfunction "VSS_PAD_P$88") (pintype "bidirectional"))
      (node (ref "U$1") (pin "P$89") (pinfunction "VSS_PAD_P$89") (pintype "bidirectional"))
      (node (ref "U$1") (pin "P$90") (pinfunction "VSS_PAD_P$90") (pintype "bidirectional"))
      (node (ref "U$1") (pin "P$B7") (pinfunction "VSS_P$B7") (pintype "power_in"))
      (node (ref "U$1") (pin "P$F23") (pinfunction "VSS_PA_P$F23") (pintype "bidirectional"))
      (node (ref "U1") (pin "1") (pinfunction "CTG_1") (pintype "power_in"))
      (node (ref "U1") (pin "4") (pinfunction "GND_4") (pintype "power_in"))
      (node (ref "U1") (pin "6") (pinfunction "QSTRT_6") (pintype "input"))
      (node (ref "U1") (pin "9") (pinfunction "EP_9") (pintype "power_in"))
      (node (ref "X1") (pin "2") (pinfunction "2_2") (pintype "passive"))
      (node (ref "X1") (pin "4") (pinfunction "4_4") (pintype "passive"))
    )
    (net (code "19") (name "HAPTIC_EN") (class "Default")
      (node (ref "IC4") (pin "A1") (pinfunction "EN_A1") (pintype "bidirectional"))
      (node (ref "U$1") (pin "P$U1") (pinfunction "P0.12_P$U1") (pintype "bidirectional"))
    )
    (net (code "20") (name "IMU_INT1") (class "Default")
      (node (ref "IC3") (pin "5") (pinfunction "INT1_5") (pintype "bidirectional"))
      (node (ref "U$1") (pin "P$N1") (pinfunction "P0.08_P$N1") (pintype "bidirectional"))
    )
    (net (code "21") (name "IMU_INT2") (class "Default")
      (node (ref "IC3") (pin "6") (pinfunction "INT2_6") (pintype "bidirectional"))
      (node (ref "U$1") (pin "P$P2") (pinfunction "P1.08_P$P2") (pintype "bidirectional"))
    )
    (net (code "22") (name "LX1") (class "Default")
      (node (ref "IC2") (pin "B2") (pinfunction "SW1_1_B2") (pintype "bidirectional"))
      (node (ref "IC2") (pin "B3") (pinfunction "SW1_2_B3") (pintype "bidirectional"))
      (node (ref "L7") (pin "1") (pinfunction "1_1") (pintype "bidirectional"))
    )
    (net (code "23") (name "LX2") (class "Default")
      (node (ref "IC2") (pin "D2") (pinfunction "SW2_1_D2") (pintype "bidirectional"))
      (node (ref "IC2") (pin "D3") (pinfunction "SW2_2_D3") (pintype "bidirectional"))
      (node (ref "L7") (pin "2") (pinfunction "2_2") (pintype "bidirectional"))
    )
    (net (code "24") (name "MOSI") (class "Default")
      (node (ref "J2") (pin "14") (pinfunction "14_14") (pintype "bidirectional"))
      (node (ref "U$1") (pin "P$B13") (pinfunction "P0.03/AIN1_P$B13") (pintype "bidirectional"))
    )
    (net (code "25") (name "Net-(D2-K)") (class "Default")
      (node (ref "C2-EP-DR") (pin "1") (pinfunction "1_1") (pintype "passive"))
      (node (ref "D2") (pin "1") (pinfunction "K_1") (pintype "bidirectional"))
      (node (ref "D4") (pin "2") (pinfunction "A_2") (pintype "bidirectional"))
    )
    (net (code "26") (name "Net-(D5-A)") (class "Default")
      (node (ref "C2-EP-DR") (pin "2") (pinfunction "2_2") (pintype "passive"))
      (node (ref "D5") (pin "2") (pinfunction "A_2") (pintype "bidirectional"))
      (node (ref "L5") (pin "2") (pinfunction "2_2") (pintype "bidirectional"))
      (node (ref "Q3") (pin "3") (pinfunction "D_3") (pintype "bidirectional"))
    )
    (net (code "27") (name "Net-(EPD_C1-Pad2)") (class "Default")
      (node (ref "EPD_C1") (pin "2") (pinfunction "2_2") (pintype "passive"))
      (node (ref "J2") (pin "5") (pinfunction "5_5") (pintype "bidirectional"))
    )
    (net (code "28") (name "Net-(EPD_C2-Pad2)") (class "Default")
      (node (ref "EPD_C2") (pin "2") (pinfunction "2_2") (pintype "passive"))
      (node (ref "J2") (pin "4") (pinfunction "4_4") (pintype "bidirectional"))
    )
    (net (code "29") (name "Net-(EPD_C6-Pad2)") (class "Default")
      (node (ref "EPD_C6") (pin "2") (pinfunction "2_2") (pintype "passive"))
      (node (ref "J2") (pin "18") (pinfunction "18_18") (pintype "bidirectional"))
    )
    (net (code "30") (name "Net-(EPD_C7-Pad2)") (class "Default")
      (node (ref "EPD_C7") (pin "2") (pinfunction "2_2") (pintype "passive"))
      (node (ref "J2") (pin "19") (pinfunction "19_19") (pintype "bidirectional"))
    )
    (net (code "31") (name "Net-(EPD_C8-Pad2)") (class "Default")
      (node (ref "EPD_C8") (pin "2") (pinfunction "2_2") (pintype "passive"))
      (node (ref "J2") (pin "20") (pinfunction "20_20") (pintype "bidirectional"))
    )
    (net (code "32") (name "Net-(EPD_C11-Pad2)") (class "Default")
      (node (ref "EPD_C11") (pin "2") (pinfunction "2_2") (pintype "passive"))
      (node (ref "J2") (pin "23") (pinfunction "23_23") (pintype "bidirectional"))
    )
    (net (code "33") (name "Net-(EPD_C12-Pad2)") (class "Default")
      (node (ref "EPD_C12") (pin "2") (pinfunction "2_2") (pintype "passive"))
      (node (ref "J2") (pin "24") (pinfunction "24_24") (pintype "bidirectional"))
    )
    (net (code "34") (name "Net-(IC1-TS{slash}MR)") (class "Default")
      (node (ref "IC1") (pin "D1") (pinfunction "TS/MR_D1") (pintype "bidirectional"))
      (node (ref "R9") (pin "2") (pinfunction "2_2") (pintype "bidirectional"))
    )
    (net (code "35") (name "Net-(IC2-SCL)") (class "Default")
      (node (ref "IC2") (pin "D1") (pinfunction "SCL_D1") (pintype "bidirectional"))
      (node (ref "R4") (pin "1") (pinfunction "1_1") (pintype "bidirectional"))
    )
    (net (code "36") (name "Net-(IC2-SDA)") (class "Default")
      (node (ref "IC2") (pin "E1") (pinfunction "SDA_E1") (pintype "bidirectional"))
      (node (ref "R2") (pin "1") (pinfunction "1_1") (pintype "bidirectional"))
    )
    (net (code "37") (name "Net-(IC3-SDO)") (class "Default")
      (node (ref "IC3") (pin "1") (pinfunction "SDO_1") (pintype "bidirectional"))
      (node (ref "R3") (pin "1") (pinfunction "1_1") (pintype "bidirectional"))
    )
    (net (code "38") (name "Net-(IC4-REG)") (class "Default")
      (node (ref "C32") (pin "1") (pinfunction "1_1") (pintype "passive"))
      (node (ref "IC4") (pin "A2") (pinfunction "REG_A2") (pintype "bidirectional"))
    )
    (net (code "39") (name "Net-(J3-CC1)") (class "Default")
      (node (ref "J3") (pin "A5") (pinfunction "CC1_A5") (pintype "bidirectional"))
      (node (ref "R1_USB") (pin "2") (pinfunction "2_2") (pintype "bidirectional"))
    )
    (net (code "40") (name "Net-(J3-CC2)") (class "Default")
      (node (ref "J3") (pin "B5") (pinfunction "CC2_B5") (pintype "bidirectional"))
      (node (ref "R2_USB") (pin "1") (pinfunction "1_1") (pintype "bidirectional"))
    )
    (net (code "41") (name "Net-(L2-Pad2)") (class "Default")
      (node (ref "L2") (pin "2") (pinfunction "2_2") (pintype "bidirectional"))
      (node (ref "L3") (pin "1") (pinfunction "1_1") (pintype "bidirectional"))
    )
    (net (code "42") (name "Net-(R1_EP_DR-Pad1)") (class "Default")
      (node (ref "R1_EP_DR") (pin "1") (pinfunction "1_1") (pintype "bidirectional"))
      (node (ref "R_TYPE_SEL") (pin "2") (pinfunction "2_2") (pintype "bidirectional"))
      (node (ref "SJ1") (pin "2") (pinfunction "2_2") (pintype "passive"))
    )
    (net (code "43") (name "Net-(U$1-ANT)") (class "Default")
      (node (ref "C3") (pin "1") (pinfunction "1_1") (pintype "passive"))
      (node (ref "L1") (pin "1") (pinfunction "1_1") (pintype "bidirectional"))
      (node (ref "U$1") (pin "P$H23") (pinfunction "ANT_P$H23") (pintype "bidirectional"))
    )
    (net (code "44") (name "Net-(U$1-DCC)") (class "Default")
      (node (ref "L2") (pin "1") (pinfunction "1_1") (pintype "bidirectional"))
      (node (ref "U$1") (pin "P$B3") (pinfunction "DCC_P$B3") (pintype "output"))
    )
    (net (code "45") (name "Net-(U$1-DEC2)") (class "Default")
      (node (ref "C13") (pin "1") (pinfunction "1_1") (pintype "passive"))
      (node (ref "U$1") (pin "P$A18") (pinfunction "DEC2_P$A18") (pintype "bidirectional"))
    )
    (net (code "46") (name "Net-(U$1-DEC3V3)") (class "Default")
      (node (ref "C20") (pin "1") (pinfunction "1_1") (pintype "passive"))
      (node (ref "U$1") (pin "P$AC5") (pinfunction "DEC3V3_P$AC5") (pintype "bidirectional"))
    )
    (net (code "47") (name "Net-(U$1-DEC5)") (class "Default")
      (node (ref "C9") (pin "1") (pinfunction "1_1") (pintype "passive"))
      (node (ref "U$1") (pin "P$N24") (pinfunction "DEC5_P$N24") (pintype "bidirectional"))
    )
    (net (code "48") (name "Net-(U$1-XC1)") (class "Default")
      (node (ref "C1") (pin "1") (pinfunction "1_1") (pintype "passive"))
      (node (ref "U$1") (pin "P$B24") (pinfunction "XC1_P$B24") (pintype "input"))
      (node (ref "X1") (pin "1") (pinfunction "1_1") (pintype "passive"))
    )
    (net (code "49") (name "Net-(U$1-XC2)") (class "Default")
      (node (ref "C2") (pin "1") (pinfunction "1_1") (pintype "passive"))
      (node (ref "U$1") (pin "P$A23") (pinfunction "XC2_P$A23") (pintype "output"))
      (node (ref "X1") (pin "3") (pinfunction "3_3") (pintype "passive"))
    )
    (net (code "50") (name "OUT+") (class "Default")
      (node (ref "IC4") (pin "A3") (pinfunction "OUT+_A3") (pintype "bidirectional"))
      (node (ref "TP_OP") (pin "TP") (pinfunction "TP_TP") (pintype "input"))
    )
    (net (code "51") (name "OUT-") (class "Default")
      (node (ref "IC4") (pin "C3") (pinfunction "OUT-_C3") (pintype "bidirectional"))
      (node (ref "TP_ON") (pin "TP") (pinfunction "TP_TP") (pintype "input"))
    )
    (net (code "52") (name "P0.01{slash}XL2") (class "Default")
      (node (ref "C17") (pin "1") (pinfunction "1_1") (pintype "passive"))
      (node (ref "C18") (pin "1") (pinfunction "1_1") (pintype "passive"))
      (node (ref "C18") (pin "2") (pinfunction "2_2") (pintype "passive"))
      (node (ref "U$1") (pin "P$F2") (pinfunction "P0.01/XL2_P$F2") (pintype "bidirectional"))
      (node (ref "X2") (pin "1") (pinfunction "1_1") (pintype "passive"))
    )
    (net (code "53") (name "P0.04") (class "Default")
      (node (ref "U$1") (pin "P$J1") (pinfunction "P0.04/AIN2_P$J1") (pintype "bidirectional"))
    )
    (net (code "54") (name "P0.09") (class "Default")
      (node (ref "U$1") (pin "P$L24") (pinfunction "P0.09/NFC1_P$L24") (pintype "bidirectional"))
    )
    (net (code "55") (name "P0.13") (class "Default")
      (node (ref "C30") (pin "1") (pinfunction "1_1") (pintype "passive"))
      (node (ref "R1") (pin "1") (pinfunction "1_1") (pintype "bidirectional"))
      (node (ref "SW1") (pin "2") (pinfunction "2_2") (pintype "passive"))
      (node (ref "U$1") (pin "P$AD8") (pinfunction "P0.13_P$AD8") (pintype "bidirectional"))
    )
    (net (code "56") (name "P0.14") (class "Default")
      (node (ref "C31") (pin "1") (pinfunction "1_1") (pintype "passive"))
      (node (ref "R5") (pin "1") (pinfunction "1_1") (pintype "bidirectional"))
      (node (ref "SW2") (pin "2") (pinfunction "2_2") (pintype "passive"))
      (node (ref "U$1") (pin "P$AC9") (pinfunction "P0.14_P$AC9") (pintype "bidirectional"))
    )
    (net (code "57") (name "P0.19") (class "Default")
      (node (ref "U$1") (pin "P$AC15") (pinfunction "P0.19_P$AC15") (pintype "bidirectional"))
    )
    (net (code "58") (name "P0.20") (class "Default")
      (node (ref "U$1") (pin "P$AD16") (pinfunction "P0.20_P$AD16") (pintype "bidirectional"))
    )
    (net (code "59") (name "P0.21") (class "Default")
      (node (ref "U$1") (pin "P$AC17") (pinfunction "P0.21_P$AC17") (pintype "bidirectional"))
    )
    (net (code "60") (name "P0.22") (class "Default")
      (node (ref "U$1") (pin "P$AD18") (pinfunction "P0.22_P$AD18") (pintype "bidirectional"))
    )
    (net (code "61") (name "P0.23") (class "Default")
      (node (ref "U$1") (pin "P$AC19") (pinfunction "P0.23_P$AC19") (pintype "bidirectional"))
    )
    (net (code "62") (name "P0.24") (class "Default")
      (node (ref "U$1") (pin "P$AD20") (pinfunction "P0.24_P$AD20") (pintype "bidirectional"))
    )
    (net (code "63") (name "P0.25") (class "Default")
      (node (ref "U$1") (pin "P$AC21") (pinfunction "P0.25_P$AC21") (pintype "bidirectional"))
    )
    (net (code "64") (name "P0.26") (class "Default")
      (node (ref "U$1") (pin "P$G1") (pinfunction "P0.26_P$G1") (pintype "bidirectional"))
    )
    (net (code "65") (name "P0.27") (class "Default")
      (node (ref "U$1") (pin "P$H2") (pinfunction "P0.27_P$H2") (pintype "bidirectional"))
    )
    (net (code "66") (name "P0.28") (class "Default")
      (node (ref "U$1") (pin "P$B11") (pinfunction "P0.28/AIN4_P$B11") (pintype "bidirectional"))
    )
    (net (code "67") (name "P0.29") (class "Default")
      (node (ref "U$1") (pin "P$A10") (pinfunction "P0.29/AIN5_P$A10") (pintype "bidirectional"))
    )
    (net (code "68") (name "P0.30") (class "Default")
      (node (ref "U$1") (pin "P$B9") (pinfunction "P0.30/AIN6_P$B9") (pintype "bidirectional"))
    )
    (net (code "69") (name "P0.31") (class "Default")
      (node (ref "U$1") (pin "P$A8") (pinfunction "P0.31/AIN7_P$A8") (pintype "bidirectional"))
    )
    (net (code "70") (name "P1.01") (class "Default")
      (node (ref "Q1") (pin "1") (pinfunction "G_1") (pintype "bidirectional"))
      (node (ref "R_PWR_EPD") (pin "1") (pinfunction "1_1") (pintype "bidirectional"))
      (node (ref "U$1") (pin "P$Y23") (pinfunction "P1.01_P$Y23") (pintype "bidirectional"))
    )
    (net (code "71") (name "P1.02") (class "Default")
      (node (ref "C29") (pin "1") (pinfunction "1_1") (pintype "passive"))
      (node (ref "R6") (pin "1") (pinfunction "1_1") (pintype "bidirectional"))
      (node (ref "SW3") (pin "2") (pinfunction "2_2") (pintype "passive"))
      (node (ref "U$1") (pin "P$W24") (pinfunction "P1.02_P$W24") (pintype "bidirectional"))
    )
    (net (code "72") (name "P1.03") (class "Default")
      (node (ref "U$1") (pin "P$V23") (pinfunction "P1.03_P$V23") (pintype "bidirectional"))
    )
    (net (code "73") (name "P1.04") (class "Default")
      (node (ref "U$1") (pin "P$U24") (pinfunction "P1.04_P$U24") (pintype "bidirectional"))
    )
    (net (code "74") (name "P1.05") (class "Default")
      (node (ref "U$1") (pin "P$T23") (pinfunction "P1.05_P$T23") (pintype "bidirectional"))
    )
    (net (code "75") (name "P1.06") (class "Default")
      (node (ref "U$1") (pin "P$R24") (pinfunction "P1.06_P$R24") (pintype "bidirectional"))
    )
    (net (code "76") (name "P1.07") (class "Default")
      (node (ref "U$1") (pin "P$P23") (pinfunction "P1.07_P$P23") (pintype "bidirectional"))
    )
    (net (code "77") (name "P1.09") (class "Default")
      (node (ref "U$1") (pin "P$R1") (pinfunction "P1.09_P$R1") (pintype "bidirectional"))
    )
    (net (code "78") (name "P1.10") (class "Default")
      (node (ref "U$1") (pin "P$A20") (pinfunction "P1.10_P$A20") (pintype "bidirectional"))
    )
    (net (code "79") (name "P1.11") (class "Default")
      (node (ref "U$1") (pin "P$B19") (pinfunction "P1.11_P$B19") (pintype "bidirectional"))
    )
    (net (code "80") (name "P1.12") (class "Default")
      (node (ref "U$1") (pin "P$B17") (pinfunction "P1.12_P$B17") (pintype "bidirectional"))
    )
    (net (code "81") (name "P1.13") (class "Default")
      (node (ref "U$1") (pin "P$A16") (pinfunction "P1.13_P$A16") (pintype "bidirectional"))
    )
    (net (code "82") (name "P1.14") (class "Default")
      (node (ref "U$1") (pin "P$B15") (pinfunction "P1.14_P$B15") (pintype "bidirectional"))
    )
    (net (code "83") (name "P1.15") (class "Default")
      (node (ref "U$1") (pin "P$A14") (pinfunction "P1.15_P$A14") (pintype "bidirectional"))
    )
    (net (code "84") (name "PMIC_INT") (class "Default")
      (node (ref "IC1") (pin "A1") (pinfunction "~{INT}_A1") (pintype "bidirectional"))
      (node (ref "U$1") (pin "P$T2") (pinfunction "P0.11_P$T2") (pintype "bidirectional"))
    )
    (net (code "85") (name "PREVGH") (class "Default")
      (node (ref "D5") (pin "1") (pinfunction "K_1") (pintype "bidirectional"))
      (node (ref "EPD_C9") (pin "2") (pinfunction "2_2") (pintype "passive"))
      (node (ref "J2") (pin "21") (pinfunction "21_21") (pintype "bidirectional"))
    )
    (net (code "86") (name "PREVGL") (class "Default")
      (node (ref "D2") (pin "2") (pinfunction "A_2") (pintype "bidirectional"))
      (node (ref "EPD_C10") (pin "2") (pinfunction "2_2") (pintype "passive"))
      (node (ref "J2") (pin "22") (pinfunction "22_22") (pintype "bidirectional"))
    )
    (net (code "87") (name "RESE") (class "Default")
      (node (ref "J2") (pin "3") (pinfunction "3_3") (pintype "bidirectional"))
      (node (ref "Q3") (pin "2") (pinfunction "S_2") (pintype "bidirectional"))
      (node (ref "R1_EP_DR") (pin "2") (pinfunction "2_2") (pintype "bidirectional"))
    )
    (net (code "88") (name "RESET") (class "Default")
      (node (ref "J1") (pin "6") (pinfunction "6_6") (pintype "bidirectional"))
      (node (ref "TP_RESET") (pin "TP") (pinfunction "TP_TP") (pintype "input"))
      (node (ref "U$1") (pin "P$AC13") (pinfunction "P0.18/RESET_P$AC13") (pintype "bidirectional"))
    )
    (net (code "89") (name "SCK") (class "Default")
      (node (ref "J2") (pin "13") (pinfunction "13_13") (pintype "bidirectional"))
      (node (ref "U$1") (pin "P$A12") (pinfunction "P0.02/AIN0_P$A12") (pintype "bidirectional"))
    )
    (net (code "90") (name "SCL") (class "Default")
      (node (ref "IC1") (pin "B1") (pinfunction "SCL_B1") (pintype "bidirectional"))
      (node (ref "IC3") (pin "12") (pinfunction "SCX_12") (pintype "bidirectional"))
      (node (ref "IC4") (pin "C1") (pinfunction "SCL_C1") (pintype "bidirectional"))
      (node (ref "R17") (pin "2") (pinfunction "2_2") (pintype "bidirectional"))
      (node (ref "R4") (pin "2") (pinfunction "2_2") (pintype "bidirectional"))
      (node (ref "TP_SCL") (pin "TP") (pinfunction "TP_TP") (pintype "input"))
      (node (ref "U$1") (pin "P$M2") (pinfunction "P0.07_P$M2") (pintype "bidirectional"))
      (node (ref "U1") (pin "7") (pinfunction "SCL_7") (pintype "input"))
    )
    (net (code "91") (name "SDA") (class "Default")
      (node (ref "IC1") (pin "C1") (pinfunction "SDA_C1") (pintype "bidirectional"))
      (node (ref "IC3") (pin "2") (pinfunction "SDX_2") (pintype "bidirectional"))
      (node (ref "IC4") (pin "B2") (pinfunction "SDA_B2") (pintype "bidirectional"))
      (node (ref "R18") (pin "2") (pinfunction "2_2") (pintype "bidirectional"))
      (node (ref "R2") (pin "2") (pinfunction "2_2") (pintype "bidirectional"))
      (node (ref "TP_SDA") (pin "TP") (pinfunction "TP_TP") (pintype "input"))
      (node (ref "U$1") (pin "P$L1") (pinfunction "P0.06_P$L1") (pintype "bidirectional"))
      (node (ref "U1") (pin "8") (pinfunction "SDA_8") (pintype "bidirectional"))
    )
    (net (code "92") (name "SWDCLK") (class "Default")
      (node (ref "J1") (pin "4") (pinfunction "4_4") (pintype "bidirectional"))
      (node (ref "TP_SWDCLK") (pin "TP") (pinfunction "TP_TP") (pintype "input"))
      (node (ref "U$1") (pin "P$AC24") (pinfunction "SWDIO_P$AC24") (pintype "bidirectional"))
    )
    (net (code "93") (name "SWDIO") (class "Default")
      (node (ref "J1") (pin "2") (pinfunction "2_2") (pintype "bidirectional"))
      (node (ref "TP_SWDIO") (pin "TP") (pinfunction "TP_TP") (pintype "input"))
      (node (ref "U$1") (pin "P$AA24") (pinfunction "SWDCLK_P$AA24") (pintype "input"))
    )
    (net (code "94") (name "SWO") (class "Default")
      (node (ref "TP_SW0") (pin "TP") (pinfunction "TP_TP") (pintype "input"))
      (node (ref "U$1") (pin "P$AD22") (pinfunction "P1.00_P$AD22") (pintype "bidirectional"))
    )
    (net (code "95") (name "VBAT") (class "Default")
      (node (ref "C27") (pin "1") (pinfunction "1_1") (pintype "passive"))
      (node (ref "C37") (pin "1") (pinfunction "1_1") (pintype "passive"))
      (node (ref "IC1") (pin "C2") (pinfunction "BAT_C2") (pintype "bidirectional"))
      (node (ref "TP_VBAT") (pin "TP") (pinfunction "TP_TP") (pintype "input"))
      (node (ref "U1") (pin "2") (pinfunction "CELL_2") (pintype "power_in"))
      (node (ref "U1") (pin "3") (pinfunction "VDD_3") (pintype "power_in"))
    )
    (net (code "96") (name "VBUS") (class "Default")
      (node (ref "C21") (pin "1") (pinfunction "1_1") (pintype "passive"))
      (node (ref "C38") (pin "1") (pinfunction "1_1") (pintype "passive"))
      (node (ref "C42") (pin "1") (pinfunction "1_1") (pintype "passive"))
      (node (ref "C43") (pin "1") (pinfunction "1_1") (pintype "passive"))
      (node (ref "D1") (pin "5") (pinfunction "VBUS_5") (pintype "bidirectional"))
      (node (ref "IC1") (pin "A2") (pinfunction "IN_A2") (pintype "bidirectional"))
      (node (ref "J3") (pin "A4_B9") (pinfunction "VBUS_A4_B9") (pintype "power_in"))
      (node (ref "J3") (pin "A9_B4") (pinfunction "VBUS_A9_B4") (pintype "power_in"))
      (node (ref "U$1") (pin "P$AD2") (pinfunction "VBUS_P$AD2") (pintype "power_in"))
    )
    (net (code "97") (name "VREG") (class "Default")
      (node (ref "C23") (pin "2") (pinfunction "2_2") (pintype "passive"))
      (node (ref "C24") (pin "2") (pinfunction "2_2") (pintype "passive"))
      (node (ref "C39") (pin "1") (pinfunction "1_1") (pintype "passive"))
      (node (ref "IC1") (pin "B2") (pinfunction "SYS_B2") (pintype "bidirectional"))
      (node (ref "IC2") (pin "A1") (pinfunction "EN_A1") (pintype "bidirectional"))
      (node (ref "IC2") (pin "A2") (pinfunction "VIN_1_A2") (pintype "bidirectional"))
      (node (ref "IC2") (pin "A3") (pinfunction "VIN_2_A3") (pintype "bidirectional"))
      (node (ref "TP2") (pin "TP") (pinfunction "TP_TP") (pintype "input"))
    )
    (net (code "98") (name "unconnected-(ANT1-NC-Pad2)") (class "Default")
      (node (ref "ANT1") (pin "2") (pinfunction "NC_2") (pintype "no_connect"))
    )
    (net (code "99") (name "unconnected-(IC3-ASCL-Pad11)") (class "Default")
      (node (ref "IC3") (pin "11") (pinfunction "ASCL_11") (pintype "bidirectional"))
    )
    (net (code "100") (name "unconnected-(IC3-ASDA-Pad4)") (class "Default")
      (node (ref "IC3") (pin "4") (pinfunction "ASDA_4") (pintype "bidirectional"))
    )
    (net (code "101") (name "unconnected-(J2-Pad1)") (class "Default")
      (node (ref "J2") (pin "1") (pinfunction "1_1") (pintype "bidirectional"))
    )
    (net (code "102") (name "unconnected-(J2-Pad6)") (class "Default")
      (node (ref "J2") (pin "6") (pinfunction "6_6") (pintype "bidirectional"))
    )
    (net (code "103") (name "unconnected-(J2-Pad7)") (class "Default")
      (node (ref "J2") (pin "7") (pinfunction "7_7") (pintype "bidirectional"))
    )
    (net (code "104") (name "unconnected-(J3-SBU1-PadA8)") (class "Default")
      (node (ref "J3") (pin "A8") (pinfunction "SBU1_A8") (pintype "bidirectional"))
    )
    (net (code "105") (name "unconnected-(J3-SBU2-PadB8)") (class "Default")
      (node (ref "J3") (pin "B8") (pinfunction "SBU2_B8") (pintype "bidirectional"))
    )
    (net (code "106") (name "unconnected-(U$1-DCCH-PadP$AB2)") (class "Default")
      (node (ref "U$1") (pin "P$AB2") (pinfunction "DCCH_P$AB2") (pintype "bidirectional"))
    )
  )
)
